# MotionDetectorCamera-Rev4.net
KiCad netlist of a schematic drawn in EAGLE
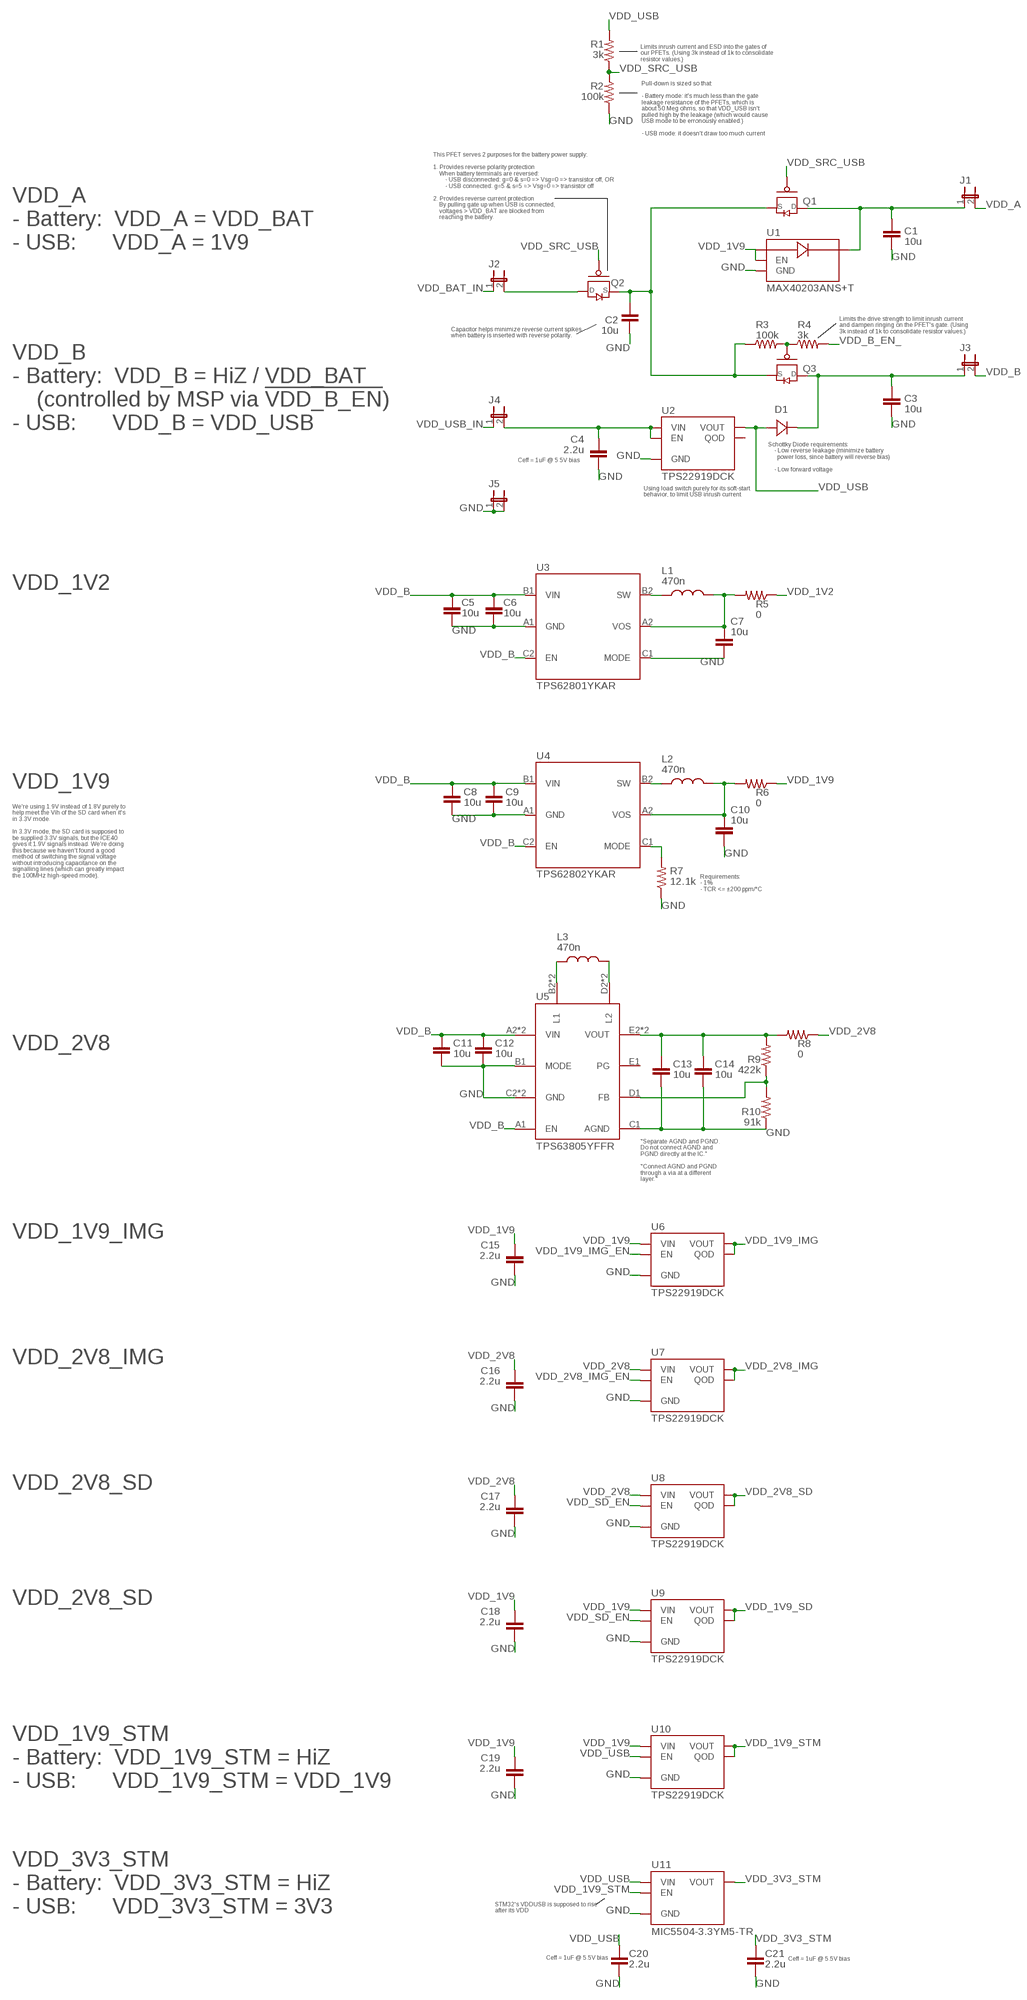
[diagram p0: schematic, sheet 1]
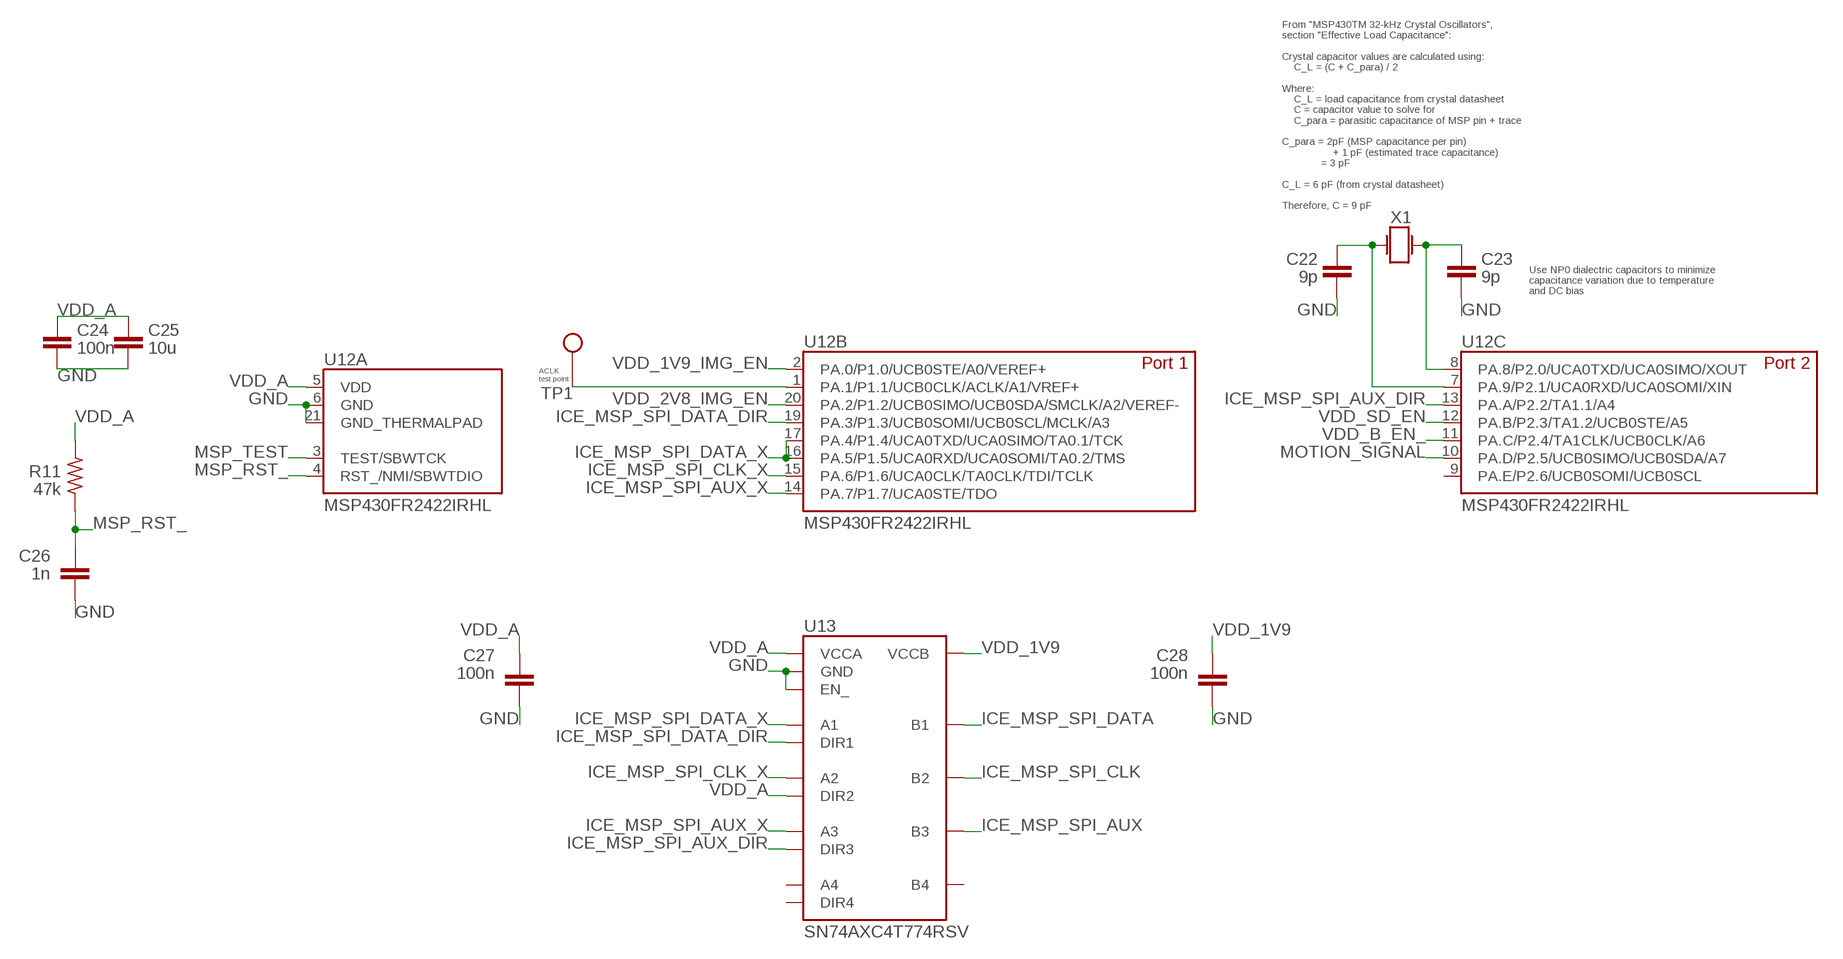
[diagram p1: schematic, sheet 2]
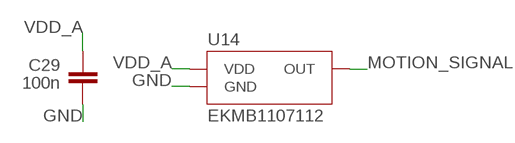
[diagram p2: schematic, sheet 3]
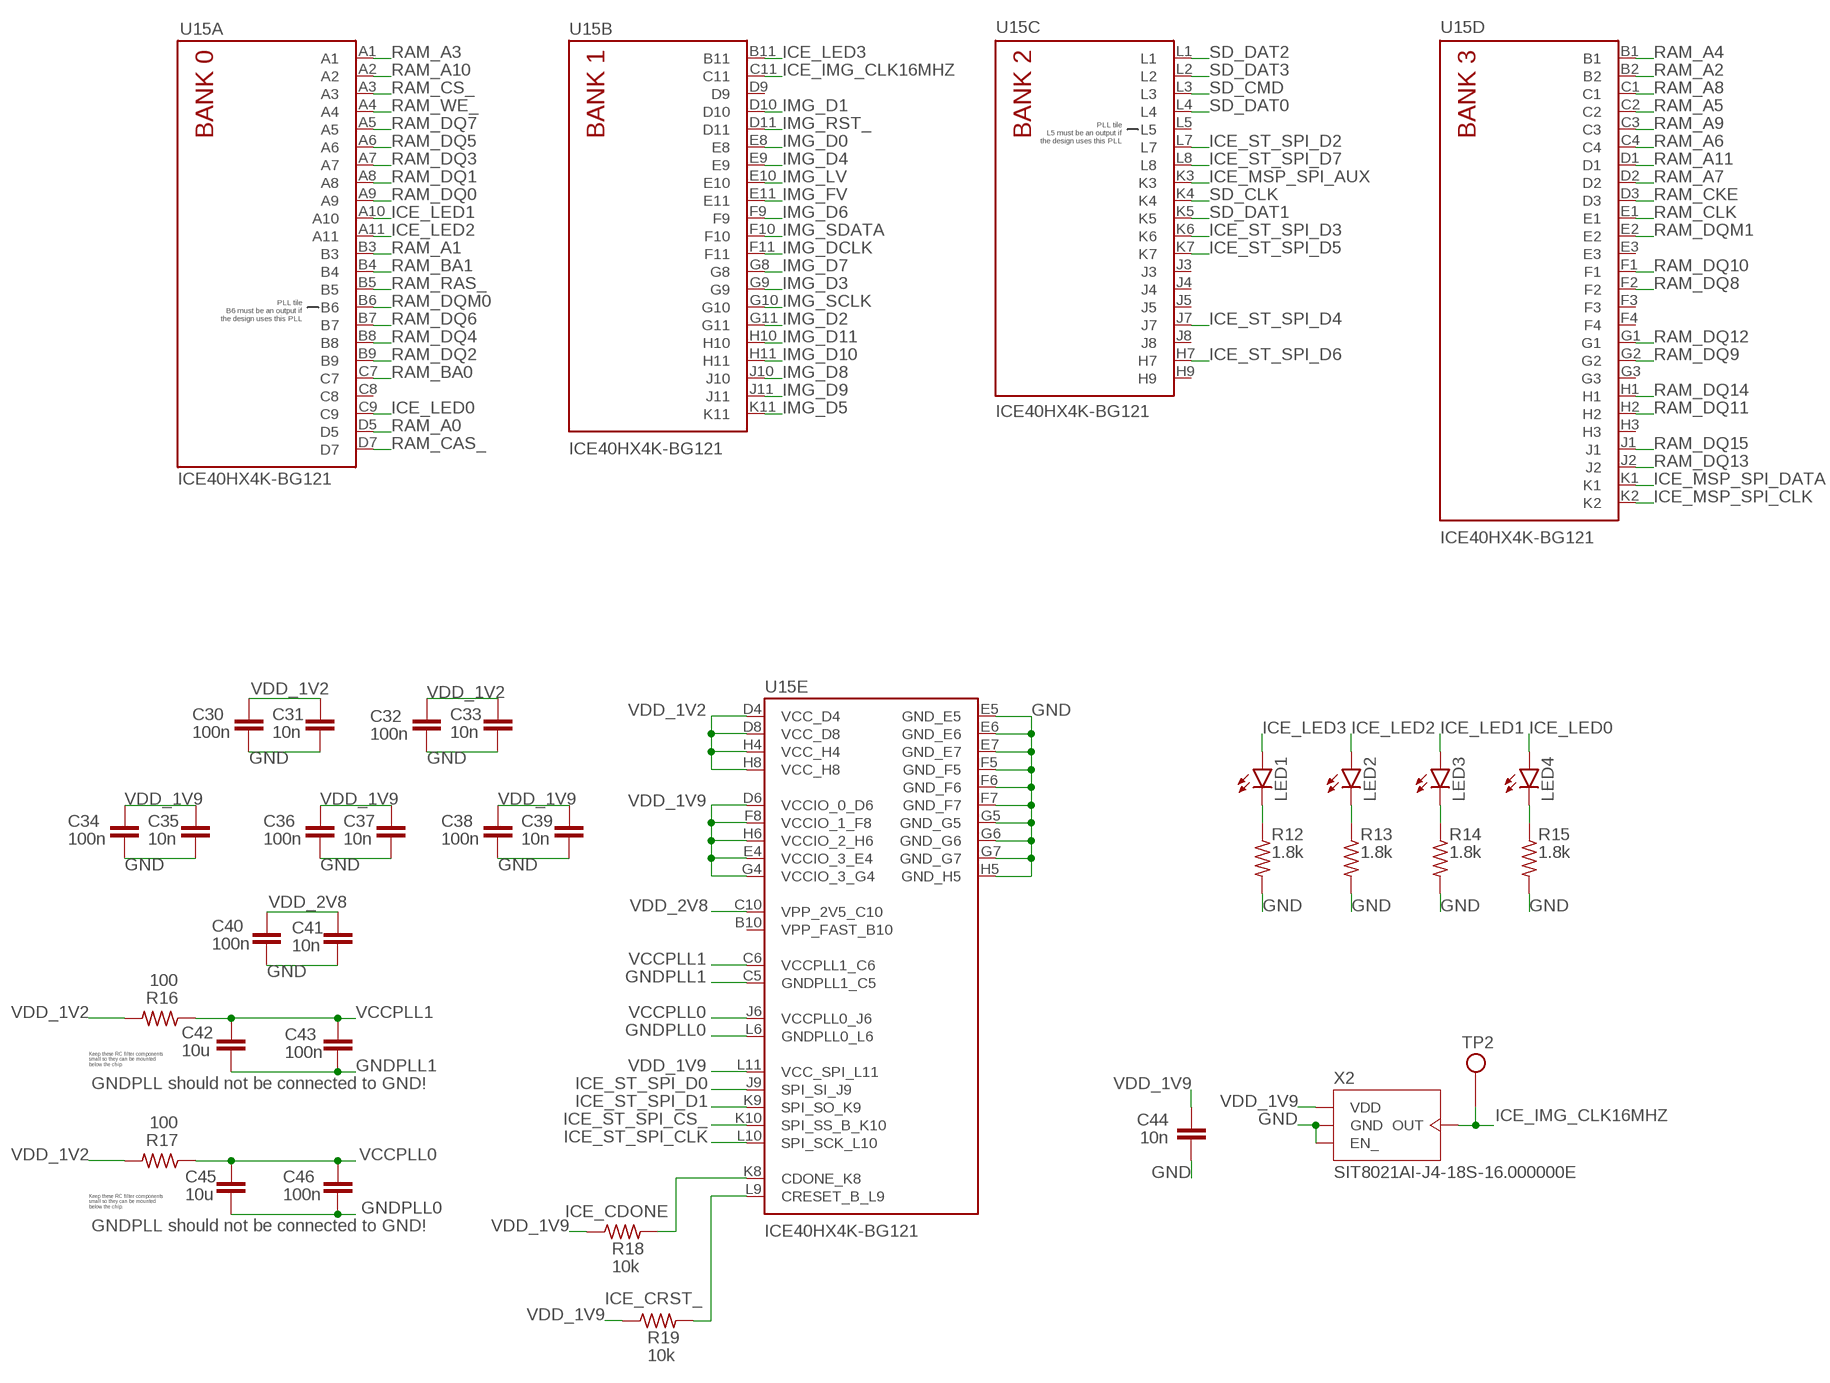
[diagram p3: schematic, sheet 4]
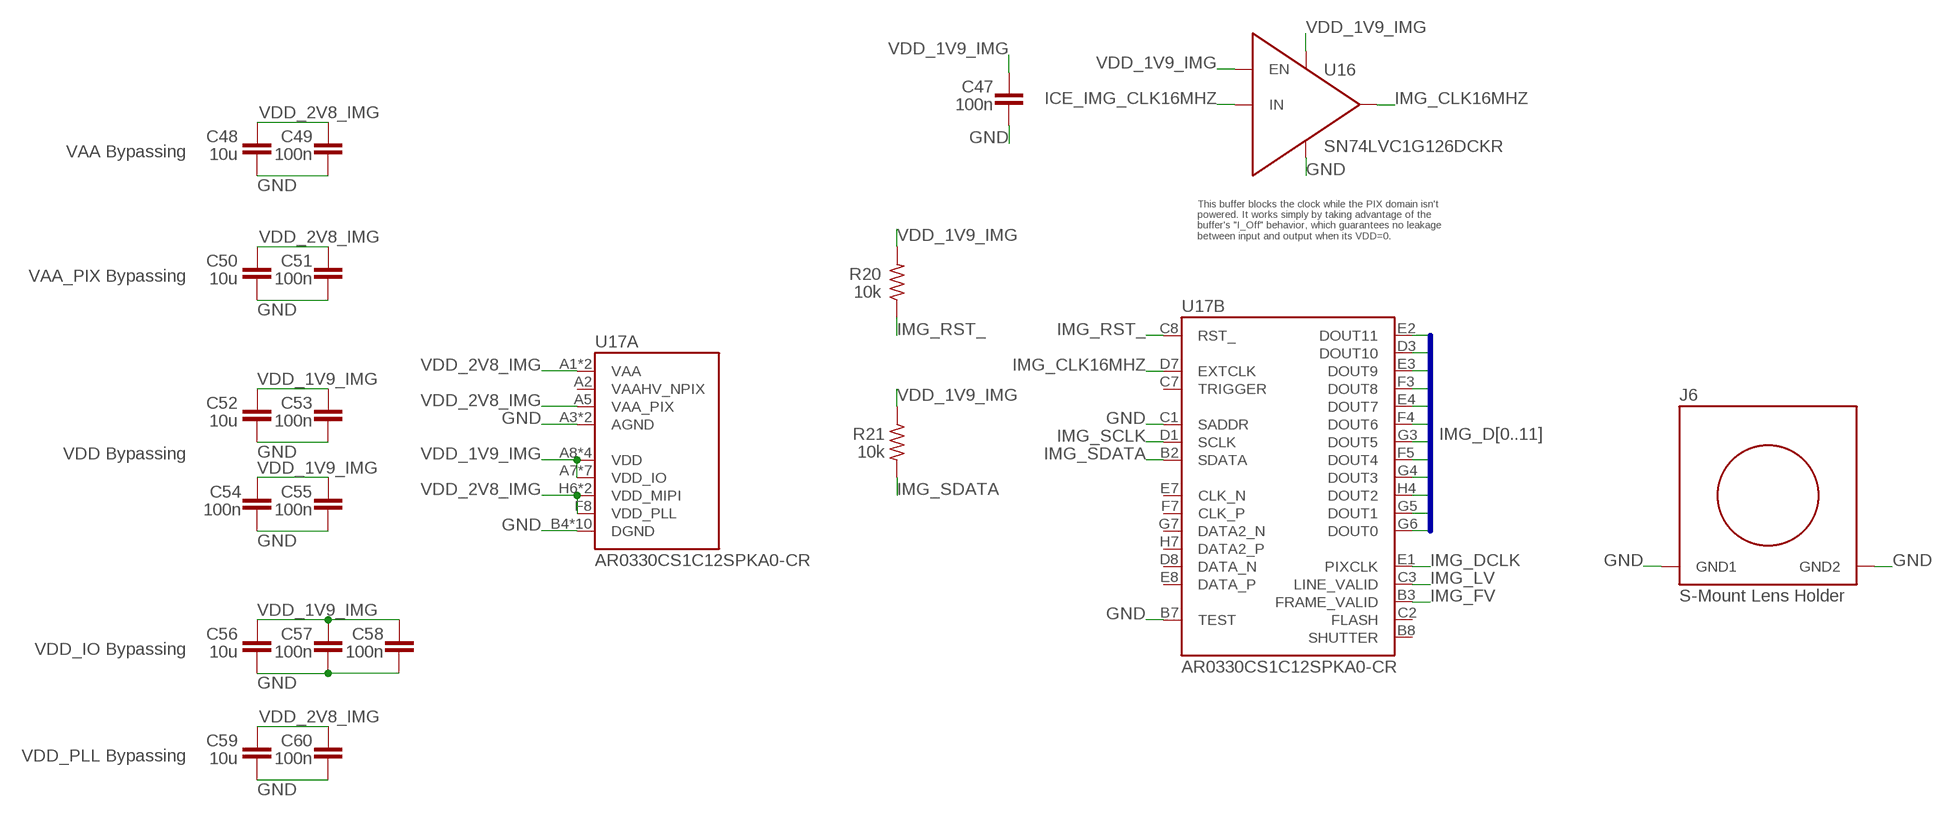
[diagram p4: schematic, sheet 5]
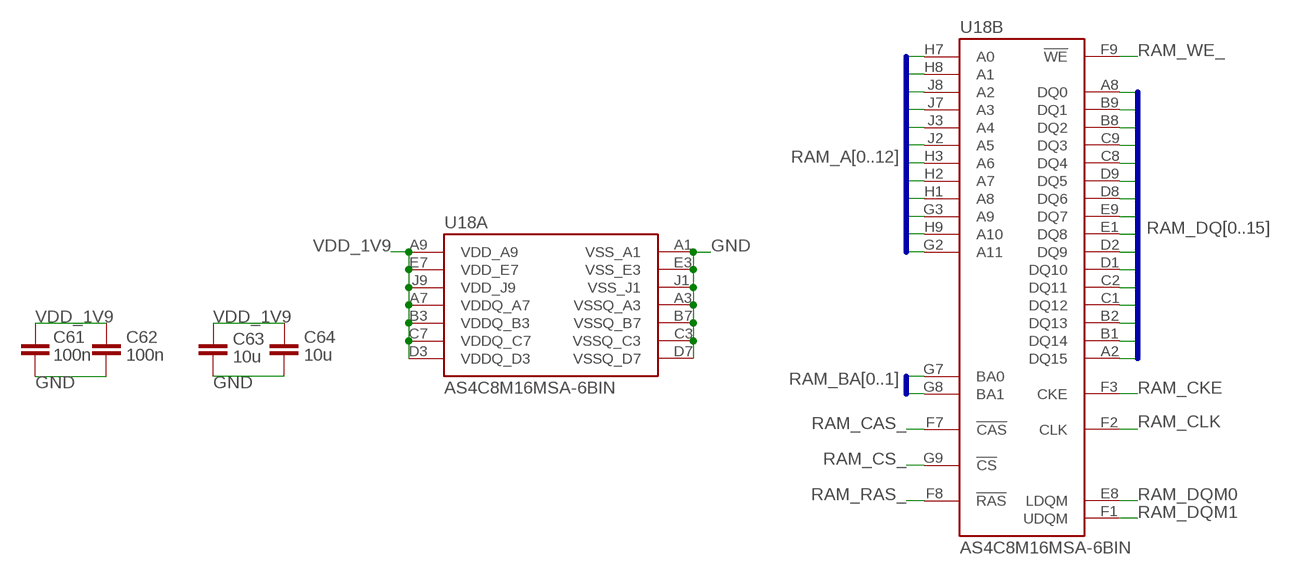
[diagram p5: schematic, sheet 6]
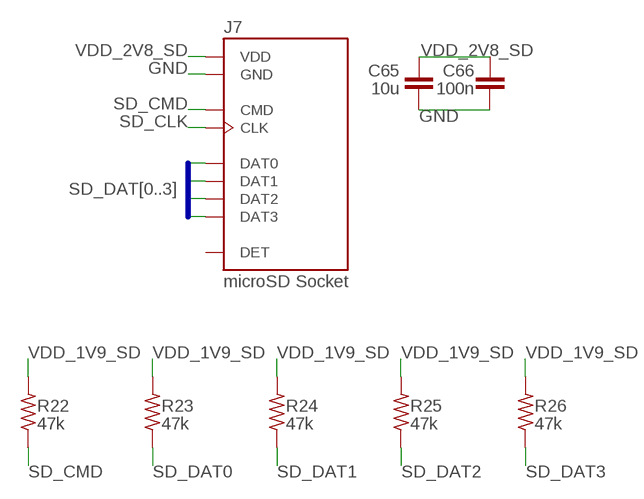
[diagram p6: schematic, sheet 7]
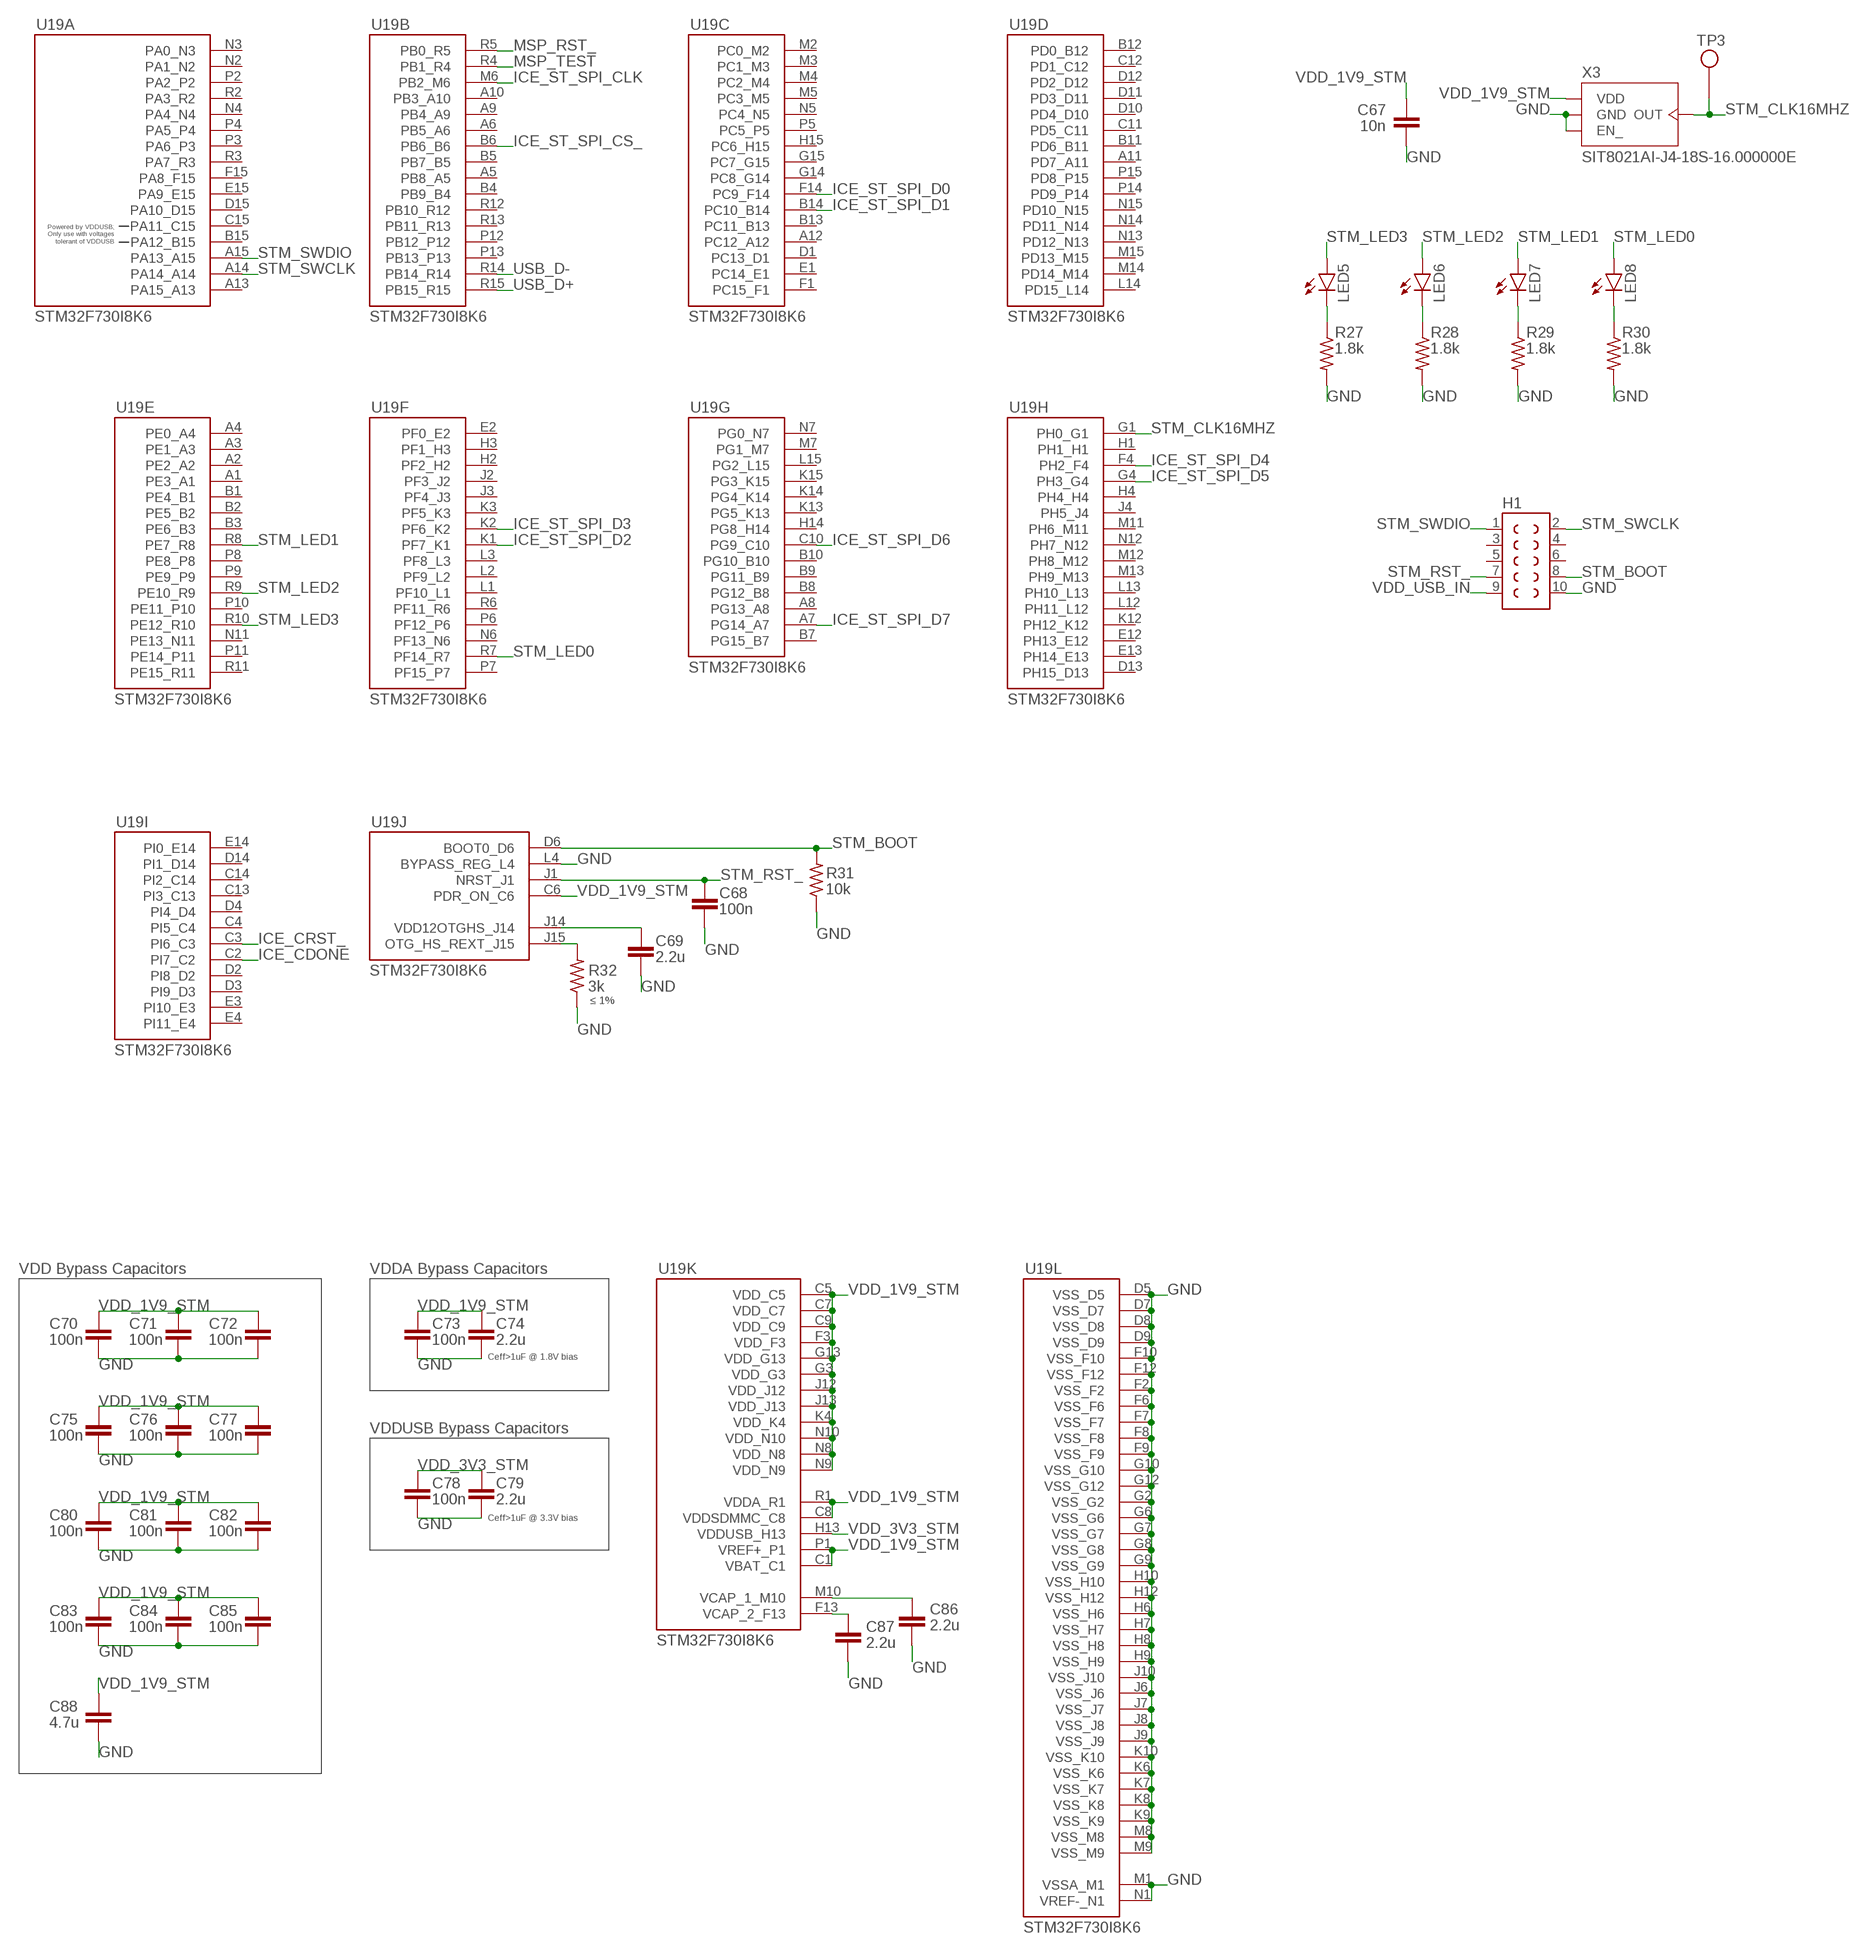
[diagram p7: schematic, sheet 8]
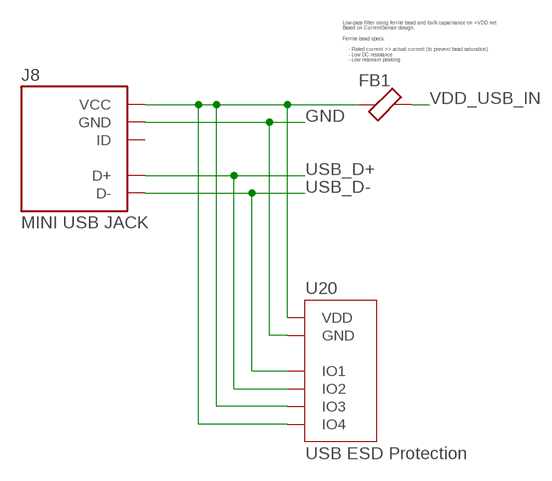
[diagram p8: schematic, sheet 9]

(export (version "E")
  (design (tool "Eeschema 10.0.6"))
  (components
    (comp (ref "C1")
      (value "10u")
      (footprint "eagle-import:0805")
      (fields (field (name "MFG") "Samsung"))
      (libsource (lib "eagle-import") (part "CAPACITOR0805"))
    )
    (comp (ref "C2")
      (value "10u")
      (footprint "eagle-import:0805")
      (fields (field (name "MFG") "Samsung"))
      (libsource (lib "eagle-import") (part "CAPACITOR0805"))
    )
    (comp (ref "C3")
      (value "10u")
      (footprint "eagle-import:0805")
      (fields (field (name "MFG") "Samsung"))
      (libsource (lib "eagle-import") (part "CAPACITOR0805"))
    )
    (comp (ref "C4")
      (value "2.2u")
      (footprint "eagle-import:0402")
      (fields (field (name "MFG") "Taiyo Yuden"))
      (libsource (lib "eagle-import") (part "CAPACITOR0402"))
    )
    (comp (ref "C5")
      (value "10u")
      (footprint "eagle-import:0805")
      (fields (field (name "MFG") "Samsung"))
      (libsource (lib "eagle-import") (part "CAPACITOR0805"))
    )
    (comp (ref "C6")
      (value "10u")
      (footprint "eagle-import:0805")
      (fields (field (name "MFG") "Samsung"))
      (libsource (lib "eagle-import") (part "CAPACITOR0805"))
    )
    (comp (ref "C7")
      (value "10u")
      (footprint "eagle-import:0805")
      (fields (field (name "MFG") "Samsung"))
      (libsource (lib "eagle-import") (part "CAPACITOR0805"))
    )
    (comp (ref "C8")
      (value "10u")
      (footprint "eagle-import:0805")
      (fields (field (name "MFG") "Samsung"))
      (libsource (lib "eagle-import") (part "CAPACITOR0805"))
    )
    (comp (ref "C9")
      (value "10u")
      (footprint "eagle-import:0805")
      (fields (field (name "MFG") "Samsung"))
      (libsource (lib "eagle-import") (part "CAPACITOR0805"))
    )
    (comp (ref "C10")
      (value "10u")
      (footprint "eagle-import:0805")
      (fields (field (name "MFG") "Samsung"))
      (libsource (lib "eagle-import") (part "CAPACITOR0805"))
    )
    (comp (ref "C11")
      (value "10u")
      (footprint "eagle-import:0805")
      (fields (field (name "MFG") "Samsung"))
      (libsource (lib "eagle-import") (part "CAPACITOR0805"))
    )
    (comp (ref "C12")
      (value "10u")
      (footprint "eagle-import:0805")
      (fields (field (name "MFG") "Samsung"))
      (libsource (lib "eagle-import") (part "CAPACITOR0805"))
    )
    (comp (ref "C13")
      (value "10u")
      (footprint "eagle-import:0805")
      (fields (field (name "MFG") "Samsung"))
      (libsource (lib "eagle-import") (part "CAPACITOR0805"))
    )
    (comp (ref "C14")
      (value "10u")
      (footprint "eagle-import:0805")
      (fields (field (name "MFG") "Samsung"))
      (libsource (lib "eagle-import") (part "CAPACITOR0805"))
    )
    (comp (ref "C15")
      (value "2.2u")
      (footprint "eagle-import:0402")
      (fields (field (name "MFG") "Taiyo Yuden"))
      (libsource (lib "eagle-import") (part "CAPACITOR0402"))
    )
    (comp (ref "C16")
      (value "2.2u")
      (footprint "eagle-import:0402")
      (fields (field (name "MFG") "Taiyo Yuden"))
      (libsource (lib "eagle-import") (part "CAPACITOR0402"))
    )
    (comp (ref "C17")
      (value "2.2u")
      (footprint "eagle-import:0402")
      (fields (field (name "MFG") "Taiyo Yuden"))
      (libsource (lib "eagle-import") (part "CAPACITOR0402"))
    )
    (comp (ref "C18")
      (value "2.2u")
      (footprint "eagle-import:0402")
      (fields (field (name "MFG") "Taiyo Yuden"))
      (libsource (lib "eagle-import") (part "CAPACITOR0402"))
    )
    (comp (ref "C19")
      (value "2.2u")
      (footprint "eagle-import:0402")
      (fields (field (name "MFG") "Taiyo Yuden"))
      (libsource (lib "eagle-import") (part "CAPACITOR0402"))
    )
    (comp (ref "C20")
      (value "2.2u")
      (footprint "eagle-import:0402")
      (fields (field (name "MFG") "Taiyo Yuden"))
      (libsource (lib "eagle-import") (part "CAPACITOR0402"))
    )
    (comp (ref "C21")
      (value "2.2u")
      (footprint "eagle-import:0402")
      (fields (field (name "MFG") "Taiyo Yuden"))
      (libsource (lib "eagle-import") (part "CAPACITOR0402"))
    )
    (comp (ref "D1")
      (value "ROHM-RB168MM-40TFTR")
      (footprint "eagle-import:ROHM-RB168MM-40TFTR")
      (fields (field (name "MFG") "ROHM"))
      (libsource (lib "eagle-import") (part "ROHM-RB168MM-40TFTR"))
    )
    (comp (ref "J1")
      (value "JUMPER")
      (footprint "eagle-import:AMPHENOL-10129380-902002ALF")
      (fields (field (name "MFG") "Amphenol"))
      (libsource (lib "eagle-import") (part "JUMPER"))
    )
    (comp (ref "J2")
      (value "JUMPER")
      (footprint "eagle-import:AMPHENOL-10129380-902002ALF")
      (fields (field (name "MFG") "Amphenol"))
      (libsource (lib "eagle-import") (part "JUMPER"))
    )
    (comp (ref "J3")
      (value "JUMPER")
      (footprint "eagle-import:AMPHENOL-10129380-902002ALF")
      (fields (field (name "MFG") "Amphenol"))
      (libsource (lib "eagle-import") (part "JUMPER"))
    )
    (comp (ref "J4")
      (value "JUMPER")
      (footprint "eagle-import:AMPHENOL-10129380-902002ALF")
      (fields (field (name "MFG") "Amphenol"))
      (libsource (lib "eagle-import") (part "JUMPER"))
    )
    (comp (ref "J5")
      (value "JUMPER")
      (footprint "eagle-import:AMPHENOL-10129380-902002ALF")
      (fields (field (name "MFG") "Amphenol"))
      (libsource (lib "eagle-import") (part "JUMPER"))
    )
    (comp (ref "L1")
      (value "470n")
      (footprint "eagle-import:0806")
      (fields (field (name "MFG") "Murata"))
      (libsource (lib "eagle-import") (part "INDUCTOR0806"))
    )
    (comp (ref "L2")
      (value "470n")
      (footprint "eagle-import:0806")
      (fields (field (name "MFG") "Murata"))
      (libsource (lib "eagle-import") (part "INDUCTOR0806"))
    )
    (comp (ref "L3")
      (value "470n")
      (footprint "eagle-import:0806")
      (fields (field (name "MFG") "Murata"))
      (libsource (lib "eagle-import") (part "INDUCTOR0806"))
    )
    (comp (ref "Q1")
      (value "PMOS-NEXPERIA-SOT1220")
      (footprint "eagle-import:NEXPERIA-SOT1220")
      (fields (field (name "MFG") "Nexperia"))
      (libsource (lib "eagle-import") (part "PMOS-NEXPERIA-SOT1220"))
    )
    (comp (ref "Q2")
      (value "PMOS-NEXPERIA-SOT1220")
      (footprint "eagle-import:NEXPERIA-SOT1220")
      (fields (field (name "MFG") "Nexperia"))
      (libsource (lib "eagle-import") (part "PMOS-NEXPERIA-SOT1220"))
    )
    (comp (ref "Q3")
      (value "PMOS-NEXPERIA-SOT1220")
      (footprint "eagle-import:NEXPERIA-SOT1220")
      (fields (field (name "MFG") "Nexperia"))
      (libsource (lib "eagle-import") (part "PMOS-NEXPERIA-SOT1220"))
    )
    (comp (ref "R1")
      (value "3k")
      (footprint "eagle-import:0402")
      (fields (field (name "MFG") "Yageo"))
      (libsource (lib "eagle-import") (part "RESISTOR0402"))
    )
    (comp (ref "R2")
      (value "100k")
      (footprint "eagle-import:0402")
      (fields (field (name "MFG") "Yageo"))
      (libsource (lib "eagle-import") (part "RESISTOR0402"))
    )
    (comp (ref "R3")
      (value "100k")
      (footprint "eagle-import:0402")
      (fields (field (name "MFG") "Yageo"))
      (libsource (lib "eagle-import") (part "RESISTOR0402"))
    )
    (comp (ref "R4")
      (value "3k")
      (footprint "eagle-import:0402")
      (fields (field (name "MFG") "Yageo"))
      (libsource (lib "eagle-import") (part "RESISTOR0402"))
    )
    (comp (ref "R5")
      (value "0")
      (footprint "eagle-import:0805")
      (fields (field (name "MFG") "Yageo"))
      (libsource (lib "eagle-import") (part "RESISTOR0805"))
    )
    (comp (ref "R6")
      (value "0")
      (footprint "eagle-import:0805")
      (fields (field (name "MFG") "Yageo"))
      (libsource (lib "eagle-import") (part "RESISTOR0805"))
    )
    (comp (ref "R7")
      (value "12.1k")
      (footprint "eagle-import:0402")
      (fields (field (name "MFG") "Walsin"))
      (libsource (lib "eagle-import") (part "RESISTOR0402"))
    )
    (comp (ref "R8")
      (value "0")
      (footprint "eagle-import:0805")
      (fields (field (name "MFG") "Yageo"))
      (libsource (lib "eagle-import") (part "RESISTOR0805"))
    )
    (comp (ref "R9")
      (value "422k")
      (footprint "eagle-import:0402")
      (fields (field (name "MFG") "Bourns"))
      (libsource (lib "eagle-import") (part "RESISTOR0402"))
    )
    (comp (ref "R10")
      (value "91k")
      (footprint "eagle-import:0402")
      (fields (field (name "MFG") "Bourns"))
      (libsource (lib "eagle-import") (part "RESISTOR0402"))
    )
    (comp (ref "U1")
      (value "MAXIM-MAX40203ANS+T")
      (footprint "eagle-import:MAXIM-MAX40203ANS+T")
      (fields (field (name "PN") "MAX40203ANS+T") (field (name "MFG") "Maxim Integrated"))
      (libsource (lib "eagle-import") (part "MAXIM-MAX40203ANS+T"))
    )
    (comp (ref "U2")
      (value "TI-TPS22919DCK")
      (footprint "eagle-import:TI-TPS22919DCK")
      (fields (field (name "PN") "TPS22919DCK") (field (name "MFG") "Texas Instruments"))
      (libsource (lib "eagle-import") (part "TI-TPS22919DCK"))
    )
    (comp (ref "U3")
      (value "TI-TPS6280XYKAR")
      (footprint "eagle-import:TI-TPS6280XYKAR")
      (fields (field (name "MFG") "Texas Instruments") (field (name "PN") "TPS62801YKAR"))
      (libsource (lib "eagle-import") (part "TI-TPS6280XYKAR"))
    )
    (comp (ref "U4")
      (value "TI-TPS6280XYKAR")
      (footprint "eagle-import:TI-TPS6280XYKAR")
      (fields (field (name "MFG") "Texas Instruments") (field (name "PN") "TPS62802YKAR"))
      (libsource (lib "eagle-import") (part "TI-TPS6280XYKAR"))
    )
    (comp (ref "U5")
      (value "TI-TPS63805YFFR")
      (footprint "eagle-import:TI-TPS63805YFFR")
      (fields (field (name "PN") "TPS63805YFFR") (field (name "MFG") "Texas Instruments"))
      (libsource (lib "eagle-import") (part "TI-TPS63805YFFR"))
    )
    (comp (ref "U6")
      (value "TI-TPS22919DCK")
      (footprint "eagle-import:TI-TPS22919DCK")
      (fields (field (name "PN") "TPS22919DCK") (field (name "MFG") "Texas Instruments"))
      (libsource (lib "eagle-import") (part "TI-TPS22919DCK"))
    )
    (comp (ref "U7")
      (value "TI-TPS22919DCK")
      (footprint "eagle-import:TI-TPS22919DCK")
      (fields (field (name "PN") "TPS22919DCK") (field (name "MFG") "Texas Instruments"))
      (libsource (lib "eagle-import") (part "TI-TPS22919DCK"))
    )
    (comp (ref "U8")
      (value "TI-TPS22919DCK")
      (footprint "eagle-import:TI-TPS22919DCK")
      (fields (field (name "PN") "TPS22919DCK") (field (name "MFG") "Texas Instruments"))
      (libsource (lib "eagle-import") (part "TI-TPS22919DCK"))
    )
    (comp (ref "U9")
      (value "TI-TPS22919DCK")
      (footprint "eagle-import:TI-TPS22919DCK")
      (fields (field (name "PN") "TPS22919DCK") (field (name "MFG") "Texas Instruments"))
      (libsource (lib "eagle-import") (part "TI-TPS22919DCK"))
    )
    (comp (ref "U10")
      (value "TI-TPS22919DCK")
      (footprint "eagle-import:TI-TPS22919DCK")
      (fields (field (name "PN") "TPS22919DCK") (field (name "MFG") "Texas Instruments"))
      (libsource (lib "eagle-import") (part "TI-TPS22919DCK"))
    )
    (comp (ref "U11")
      (value "MICROCHIP-MIC550X")
      (footprint "eagle-import:MICROCHIP-MIC550X-SOT23-5")
      (fields (field (name "MFG") "Microchip") (field (name "PN") "MIC5504-3.3YM5-TR"))
      (libsource (lib "eagle-import") (part "MICROCHIP-MIC550X"))
    )
    (comp (ref "C29")
      (value "100n")
      (footprint "eagle-import:0402")
      (fields (field (name "MFG") "Murata"))
      (libsource (lib "eagle-import") (part "CAPACITOR0402"))
    )
    (comp (ref "U14")
      (value "PANASONIC-EKMB110711X")
      (footprint "eagle-import:PANASONIC-EKMB110711X")
      (fields (field (name "MFG") "Panasonic") (field (name "PN") "EKMB1107112"))
      (libsource (lib "eagle-import") (part "PANASONIC-EKMB110711X"))
    )
    (comp (ref "C22")
      (value "9p")
      (footprint "eagle-import:0402")
      (fields (field (name "MFG") "Yageo"))
      (libsource (lib "eagle-import") (part "CAPACITOR0402"))
    )
    (comp (ref "C23")
      (value "9p")
      (footprint "eagle-import:0402")
      (fields (field (name "MFG") "Yageo"))
      (libsource (lib "eagle-import") (part "CAPACITOR0402"))
    )
    (comp (ref "C24")
      (value "100n")
      (footprint "eagle-import:0402")
      (fields (field (name "MFG") "Murata"))
      (libsource (lib "eagle-import") (part "CAPACITOR0402"))
    )
    (comp (ref "C25")
      (value "10u")
      (footprint "eagle-import:0805")
      (fields (field (name "MFG") "Samsung"))
      (libsource (lib "eagle-import") (part "CAPACITOR0805"))
    )
    (comp (ref "C26")
      (value "1n")
      (footprint "eagle-import:0402")
      (fields (field (name "MFG") "Yageo"))
      (libsource (lib "eagle-import") (part "CAPACITOR0402"))
    )
    (comp (ref "C27")
      (value "100n")
      (footprint "eagle-import:0402")
      (fields (field (name "MFG") "Murata"))
      (libsource (lib "eagle-import") (part "CAPACITOR0402"))
    )
    (comp (ref "C28")
      (value "100n")
      (footprint "eagle-import:0402")
      (fields (field (name "MFG") "Murata"))
      (libsource (lib "eagle-import") (part "CAPACITOR0402"))
    )
    (comp (ref "R11")
      (value "47k")
      (footprint "eagle-import:0402")
      (fields (field (name "MFG") "Walsin"))
      (libsource (lib "eagle-import") (part "RESISTOR0402"))
    )
    (comp (ref "TP1")
      (value "TEST-POINT")
      (footprint "eagle-import:TEST-POINT")
      (libsource (lib "eagle-import") (part "TEST-POINT"))
    )
    (comp (ref "U12")
      (value "TI-MSP430FR2422IRHL")
      (footprint "eagle-import:TI-MSP430FR2422IRHL")
      (fields (field (name "PN") "MSP430FR2422IRHL") (field (name "MFG") "Texas Instruments"))
      (libsource (lib "eagle-import") (part "TI-MSP430FR2422IRHL"))
    )
    (comp (ref "U13")
      (value "TI-SN74AXC4T774RSV")
      (footprint "eagle-import:TI-SN74AXC4T774RSV")
      (fields (field (name "PN") "SN74AXC4T774RSV") (field (name "MFG") "Texas Instruments"))
      (libsource (lib "eagle-import") (part "TI-SN74AXC4T774RSV"))
    )
    (comp (ref "X1")
      (value "EPSON-MC-306")
      (footprint "eagle-import:EPSON-MC-306")
      (fields (field (name "MFG") "Epson") (field (name "PN") "MC-306 32.7680K-E3:ROHS"))
      (libsource (lib "eagle-import") (part "EPSON-MC-306"))
    )
    (comp (ref "C47")
      (value "100n")
      (footprint "eagle-import:0402")
      (fields (field (name "MFG") "Murata"))
      (libsource (lib "eagle-import") (part "CAPACITOR0402"))
    )
    (comp (ref "C48")
      (value "10u")
      (footprint "eagle-import:0805")
      (fields (field (name "MFG") "Samsung"))
      (libsource (lib "eagle-import") (part "CAPACITOR0805"))
    )
    (comp (ref "C49")
      (value "100n")
      (footprint "eagle-import:0402")
      (fields (field (name "MFG") "Murata"))
      (libsource (lib "eagle-import") (part "CAPACITOR0402"))
    )
    (comp (ref "C50")
      (value "10u")
      (footprint "eagle-import:0805")
      (fields (field (name "MFG") "Samsung"))
      (libsource (lib "eagle-import") (part "CAPACITOR0805"))
    )
    (comp (ref "C51")
      (value "100n")
      (footprint "eagle-import:0402")
      (fields (field (name "MFG") "Murata"))
      (libsource (lib "eagle-import") (part "CAPACITOR0402"))
    )
    (comp (ref "C52")
      (value "10u")
      (footprint "eagle-import:0805")
      (fields (field (name "MFG") "Samsung"))
      (libsource (lib "eagle-import") (part "CAPACITOR0805"))
    )
    (comp (ref "C53")
      (value "100n")
      (footprint "eagle-import:0402")
      (fields (field (name "MFG") "Murata"))
      (libsource (lib "eagle-import") (part "CAPACITOR0402"))
    )
    (comp (ref "C54")
      (value "100n")
      (footprint "eagle-import:0402")
      (fields (field (name "MFG") "Murata"))
      (libsource (lib "eagle-import") (part "CAPACITOR0402"))
    )
    (comp (ref "C55")
      (value "100n")
      (footprint "eagle-import:0402")
      (fields (field (name "MFG") "Murata"))
      (libsource (lib "eagle-import") (part "CAPACITOR0402"))
    )
    (comp (ref "C56")
      (value "10u")
      (footprint "eagle-import:0805")
      (fields (field (name "MFG") "Samsung"))
      (libsource (lib "eagle-import") (part "CAPACITOR0805"))
    )
    (comp (ref "C57")
      (value "100n")
      (footprint "eagle-import:0402")
      (fields (field (name "MFG") "Murata"))
      (libsource (lib "eagle-import") (part "CAPACITOR0402"))
    )
    (comp (ref "C58")
      (value "100n")
      (footprint "eagle-import:0402")
      (fields (field (name "MFG") "Murata"))
      (libsource (lib "eagle-import") (part "CAPACITOR0402"))
    )
    (comp (ref "C59")
      (value "10u")
      (footprint "eagle-import:0805")
      (fields (field (name "MFG") "Samsung"))
      (libsource (lib "eagle-import") (part "CAPACITOR0805"))
    )
    (comp (ref "C60")
      (value "100n")
      (footprint "eagle-import:0402")
      (fields (field (name "MFG") "Murata"))
      (libsource (lib "eagle-import") (part "CAPACITOR0402"))
    )
    (comp (ref "J6")
      (value "S-MOUNT-LENS-HOLDER")
      (footprint "eagle-import:S-MOUNT-LENS-HOLDER")
      (fields (field (name "MFG") "Marshall Electronics"))
      (libsource (lib "eagle-import") (part "S-MOUNT-LENS-HOLDER"))
    )
    (comp (ref "R20")
      (value "10k")
      (footprint "eagle-import:0402")
      (fields (field (name "MFG") "Yageo"))
      (libsource (lib "eagle-import") (part "RESISTOR0402"))
    )
    (comp (ref "R21")
      (value "10k")
      (footprint "eagle-import:0402")
      (fields (field (name "MFG") "Yageo"))
      (libsource (lib "eagle-import") (part "RESISTOR0402"))
    )
    (comp (ref "U16")
      (value "TI-SN74LVC1G126")
      (footprint "eagle-import:TI-SN74LVC1G126DCK")
      (fields (field (name "MFG") "Texas Instruments") (field (name "PN") "SN74LVC1G126DCKR"))
      (libsource (lib "eagle-import") (part "TI-SN74LVC1G126"))
    )
    (comp (ref "U17")
      (value "ON-AR0330CS1C12SPKA0")
      (footprint "eagle-import:ON-AR0330CS1C12SPKA0")
      (fields (field (name "MFG") "ON Semiconductor") (field (name "PN") "AR0330CS1C12SPKA0-CR"))
      (libsource (lib "eagle-import") (part "ON-AR0330CS1C12SPKA0"))
    )
    (comp (ref "FB1")
      (value "FERRITE-BEAD0402")
      (footprint "eagle-import:0402")
      (fields (field (name "MFG") "Taiyo Yuden"))
      (libsource (lib "eagle-import") (part "FERRITE-BEAD0402"))
    )
    (comp (ref "J8")
      (value "MINI-USB-JACK")
      (footprint "eagle-import:AMPHENOL-10033526-N3222MLF")
      (fields (field (name "MFG") "Amphenol FCI"))
      (libsource (lib "eagle-import") (part "MINI-USB-JACK"))
    )
    (comp (ref "U20")
      (value "DIODESINC-DT1446-04V-7")
      (footprint "eagle-import:DIODESINC-DT1446-04V-7")
      (fields (field (name "MFG") "Diodes Incorporated"))
      (libsource (lib "eagle-import") (part "DIODESINC-DT1446-04V-7"))
    )
    (comp (ref "C61")
      (value "100n")
      (footprint "eagle-import:0402")
      (fields (field (name "MFG") "Murata"))
      (libsource (lib "eagle-import") (part "CAPACITOR0402"))
    )
    (comp (ref "C62")
      (value "100n")
      (footprint "eagle-import:0402")
      (fields (field (name "MFG") "Murata"))
      (libsource (lib "eagle-import") (part "CAPACITOR0402"))
    )
    (comp (ref "C63")
      (value "10u")
      (footprint "eagle-import:0805")
      (fields (field (name "MFG") "Samsung"))
      (libsource (lib "eagle-import") (part "CAPACITOR0805"))
    )
    (comp (ref "C64")
      (value "10u")
      (footprint "eagle-import:0805")
      (fields (field (name "MFG") "Samsung"))
      (libsource (lib "eagle-import") (part "CAPACITOR0805"))
    )
    (comp (ref "U18")
      (value "ALLIANCE-AS4C8M16MSA-6BIN")
      (footprint "eagle-import:ALLIANCE-AS4C8M16MSA-6BIN")
      (fields (field (name "PN") "AS4C8M16MSA-6BIN") (field (name "MFG") "Alliance Memory"))
      (libsource (lib "eagle-import") (part "ALLIANCE-AS4C8M16MSA-6BIN"))
    )
    (comp (ref "C67")
      (value "10n")
      (footprint "eagle-import:0402")
      (fields (field (name "MFG") "Samsung"))
      (libsource (lib "eagle-import") (part "CAPACITOR0402"))
    )
    (comp (ref "C68")
      (value "100n")
      (footprint "eagle-import:0402")
      (fields (field (name "MFG") "Murata"))
      (libsource (lib "eagle-import") (part "CAPACITOR0402"))
    )
    (comp (ref "C69")
      (value "2.2u")
      (footprint "eagle-import:0402")
      (fields (field (name "MFG") "Taiyo Yuden"))
      (libsource (lib "eagle-import") (part "CAPACITOR0402"))
    )
    (comp (ref "C70")
      (value "100n")
      (footprint "eagle-import:0402")
      (fields (field (name "MFG") "Murata"))
      (libsource (lib "eagle-import") (part "CAPACITOR0402"))
    )
    (comp (ref "C71")
      (value "100n")
      (footprint "eagle-import:0402")
      (fields (field (name "MFG") "Murata"))
      (libsource (lib "eagle-import") (part "CAPACITOR0402"))
    )
    (comp (ref "C72")
      (value "100n")
      (footprint "eagle-import:0402")
      (fields (field (name "MFG") "Murata"))
      (libsource (lib "eagle-import") (part "CAPACITOR0402"))
    )
    (comp (ref "C73")
      (value "100n")
      (footprint "eagle-import:0402")
      (fields (field (name "MFG") "Murata"))
      (libsource (lib "eagle-import") (part "CAPACITOR0402"))
    )
    (comp (ref "C74")
      (value "2.2u")
      (footprint "eagle-import:0402")
      (fields (field (name "MFG") "Taiyo Yuden"))
      (libsource (lib "eagle-import") (part "CAPACITOR0402"))
    )
    (comp (ref "C75")
      (value "100n")
      (footprint "eagle-import:0402")
      (fields (field (name "MFG") "Murata"))
      (libsource (lib "eagle-import") (part "CAPACITOR0402"))
    )
    (comp (ref "C76")
      (value "100n")
      (footprint "eagle-import:0402")
      (fields (field (name "MFG") "Murata"))
      (libsource (lib "eagle-import") (part "CAPACITOR0402"))
    )
    (comp (ref "C77")
      (value "100n")
      (footprint "eagle-import:0402")
      (fields (field (name "MFG") "Murata"))
      (libsource (lib "eagle-import") (part "CAPACITOR0402"))
    )
    (comp (ref "C78")
      (value "100n")
      (footprint "eagle-import:0402")
      (fields (field (name "MFG") "Murata"))
      (libsource (lib "eagle-import") (part "CAPACITOR0402"))
    )
    (comp (ref "C79")
      (value "2.2u")
      (footprint "eagle-import:0402")
      (fields (field (name "MFG") "Taiyo Yuden"))
      (libsource (lib "eagle-import") (part "CAPACITOR0402"))
    )
    (comp (ref "C80")
      (value "100n")
      (footprint "eagle-import:0402")
      (fields (field (name "MFG") "Murata"))
      (libsource (lib "eagle-import") (part "CAPACITOR0402"))
    )
    (comp (ref "C81")
      (value "100n")
      (footprint "eagle-import:0402")
      (fields (field (name "MFG") "Murata"))
      (libsource (lib "eagle-import") (part "CAPACITOR0402"))
    )
    (comp (ref "C82")
      (value "100n")
      (footprint "eagle-import:0402")
      (fields (field (name "MFG") "Murata"))
      (libsource (lib "eagle-import") (part "CAPACITOR0402"))
    )
    (comp (ref "C83")
      (value "100n")
      (footprint "eagle-import:0402")
      (fields (field (name "MFG") "Murata"))
      (libsource (lib "eagle-import") (part "CAPACITOR0402"))
    )
    (comp (ref "C84")
      (value "100n")
      (footprint "eagle-import:0402")
      (fields (field (name "MFG") "Murata"))
      (libsource (lib "eagle-import") (part "CAPACITOR0402"))
    )
    (comp (ref "C85")
      (value "100n")
      (footprint "eagle-import:0402")
      (fields (field (name "MFG") "Murata"))
      (libsource (lib "eagle-import") (part "CAPACITOR0402"))
    )
    (comp (ref "C86")
      (value "2.2u")
      (footprint "eagle-import:0402")
      (fields (field (name "MFG") "Taiyo Yuden"))
      (libsource (lib "eagle-import") (part "CAPACITOR0402"))
    )
    (comp (ref "C87")
      (value "2.2u")
      (footprint "eagle-import:0402")
      (fields (field (name "MFG") "Taiyo Yuden"))
      (libsource (lib "eagle-import") (part "CAPACITOR0402"))
    )
    (comp (ref "C88")
      (value "4.7u")
      (footprint "eagle-import:0603")
      (fields (field (name "MFG") "Taiyo Yuden"))
      (libsource (lib "eagle-import") (part "CAPACITOR0603"))
    )
    (comp (ref "H1")
      (value "HEADER-2X5")
      (footprint "eagle-import:TEC-1-2314844-0")
      (fields (field (name "MFG") "TE Connectivity"))
      (libsource (lib "eagle-import") (part "HEADER-2X5"))
    )
    (comp (ref "LED5")
      (value "LED")
      (footprint "eagle-import:LED-0603")
      (fields (field (name "MFG") "OSRAM"))
      (libsource (lib "eagle-import") (part "LED"))
    )
    (comp (ref "LED6")
      (value "LED")
      (footprint "eagle-import:LED-0603")
      (fields (field (name "MFG") "OSRAM"))
      (libsource (lib "eagle-import") (part "LED"))
    )
    (comp (ref "LED7")
      (value "LED")
      (footprint "eagle-import:LED-0603")
      (fields (field (name "MFG") "OSRAM"))
      (libsource (lib "eagle-import") (part "LED"))
    )
    (comp (ref "LED8")
      (value "LED")
      (footprint "eagle-import:LED-0603")
      (fields (field (name "MFG") "OSRAM"))
      (libsource (lib "eagle-import") (part "LED"))
    )
    (comp (ref "R27")
      (value "1.8k")
      (footprint "eagle-import:0402")
      (fields (field (name "MFG") "TE Connectivity"))
      (libsource (lib "eagle-import") (part "RESISTOR0402"))
    )
    (comp (ref "R28")
      (value "1.8k")
      (footprint "eagle-import:0402")
      (fields (field (name "MFG") "TE Connectivity"))
      (libsource (lib "eagle-import") (part "RESISTOR0402"))
    )
    (comp (ref "R29")
      (value "1.8k")
      (footprint "eagle-import:0402")
      (fields (field (name "MFG") "TE Connectivity"))
      (libsource (lib "eagle-import") (part "RESISTOR0402"))
    )
    (comp (ref "R30")
      (value "1.8k")
      (footprint "eagle-import:0402")
      (fields (field (name "MFG") "TE Connectivity"))
      (libsource (lib "eagle-import") (part "RESISTOR0402"))
    )
    (comp (ref "R31")
      (value "10k")
      (footprint "eagle-import:0402")
      (fields (field (name "MFG") "Yageo"))
      (libsource (lib "eagle-import") (part "RESISTOR0402"))
    )
    (comp (ref "R32")
      (value "3k")
      (footprint "eagle-import:0402")
      (fields (field (name "MFG") "Yageo"))
      (libsource (lib "eagle-import") (part "RESISTOR0402"))
    )
    (comp (ref "TP3")
      (value "TEST-POINT")
      (footprint "eagle-import:TEST-POINT")
      (libsource (lib "eagle-import") (part "TEST-POINT"))
    )
    (comp (ref "U19")
      (value "STM-STM32F730")
      (footprint "eagle-import:STM-STM32F730I8")
      (fields (field (name "MFG") "STMicroelectronics") (field (name "PN") "STM32F730I8K6"))
      (libsource (lib "eagle-import") (part "STM-STM32F730"))
    )
    (comp (ref "X3")
      (value "SITIME-SIT8021")
      (footprint "eagle-import:SITIME-SIT8021")
      (fields (field (name "MFG") "SiTime") (field (name "PN") "SIT8021AI-J4-18S-16.000000E"))
      (libsource (lib "eagle-import") (part "SITIME-SIT8021"))
    )
    (comp (ref "C30")
      (value "100n")
      (footprint "eagle-import:0402")
      (fields (field (name "MFG") "Murata"))
      (libsource (lib "eagle-import") (part "CAPACITOR0402"))
    )
    (comp (ref "C31")
      (value "10n")
      (footprint "eagle-import:0402")
      (fields (field (name "MFG") "Samsung"))
      (libsource (lib "eagle-import") (part "CAPACITOR0402"))
    )
    (comp (ref "C32")
      (value "100n")
      (footprint "eagle-import:0402")
      (fields (field (name "MFG") "Murata"))
      (libsource (lib "eagle-import") (part "CAPACITOR0402"))
    )
    (comp (ref "C33")
      (value "10n")
      (footprint "eagle-import:0402")
      (fields (field (name "MFG") "Samsung"))
      (libsource (lib "eagle-import") (part "CAPACITOR0402"))
    )
    (comp (ref "C34")
      (value "100n")
      (footprint "eagle-import:0402")
      (fields (field (name "MFG") "Murata"))
      (libsource (lib "eagle-import") (part "CAPACITOR0402"))
    )
    (comp (ref "C35")
      (value "10n")
      (footprint "eagle-import:0402")
      (fields (field (name "MFG") "Samsung"))
      (libsource (lib "eagle-import") (part "CAPACITOR0402"))
    )
    (comp (ref "C36")
      (value "100n")
      (footprint "eagle-import:0402")
      (fields (field (name "MFG") "Murata"))
      (libsource (lib "eagle-import") (part "CAPACITOR0402"))
    )
    (comp (ref "C37")
      (value "10n")
      (footprint "eagle-import:0402")
      (fields (field (name "MFG") "Samsung"))
      (libsource (lib "eagle-import") (part "CAPACITOR0402"))
    )
    (comp (ref "C38")
      (value "100n")
      (footprint "eagle-import:0402")
      (fields (field (name "MFG") "Murata"))
      (libsource (lib "eagle-import") (part "CAPACITOR0402"))
    )
    (comp (ref "C39")
      (value "10n")
      (footprint "eagle-import:0402")
      (fields (field (name "MFG") "Samsung"))
      (libsource (lib "eagle-import") (part "CAPACITOR0402"))
    )
    (comp (ref "C40")
      (value "100n")
      (footprint "eagle-import:0402")
      (fields (field (name "MFG") "Murata"))
      (libsource (lib "eagle-import") (part "CAPACITOR0402"))
    )
    (comp (ref "C41")
      (value "10n")
      (footprint "eagle-import:0402")
      (fields (field (name "MFG") "Samsung"))
      (libsource (lib "eagle-import") (part "CAPACITOR0402"))
    )
    (comp (ref "C42")
      (value "10u")
      (footprint "eagle-import:0805")
      (fields (field (name "MFG") "Samsung"))
      (libsource (lib "eagle-import") (part "CAPACITOR0805"))
    )
    (comp (ref "C43")
      (value "100n")
      (footprint "eagle-import:0402")
      (fields (field (name "MFG") "Murata"))
      (libsource (lib "eagle-import") (part "CAPACITOR0402"))
    )
    (comp (ref "C44")
      (value "10n")
      (footprint "eagle-import:0402")
      (fields (field (name "MFG") "Samsung"))
      (libsource (lib "eagle-import") (part "CAPACITOR0402"))
    )
    (comp (ref "C45")
      (value "10u")
      (footprint "eagle-import:0805")
      (fields (field (name "MFG") "Samsung"))
      (libsource (lib "eagle-import") (part "CAPACITOR0805"))
    )
    (comp (ref "C46")
      (value "100n")
      (footprint "eagle-import:0402")
      (fields (field (name "MFG") "Murata"))
      (libsource (lib "eagle-import") (part "CAPACITOR0402"))
    )
    (comp (ref "LED1")
      (value "LED")
      (footprint "eagle-import:LED-0603")
      (fields (field (name "MFG") "OSRAM"))
      (libsource (lib "eagle-import") (part "LED"))
    )
    (comp (ref "LED2")
      (value "LED")
      (footprint "eagle-import:LED-0603")
      (fields (field (name "MFG") "OSRAM"))
      (libsource (lib "eagle-import") (part "LED"))
    )
    (comp (ref "LED3")
      (value "LED")
      (footprint "eagle-import:LED-0603")
      (fields (field (name "MFG") "OSRAM"))
      (libsource (lib "eagle-import") (part "LED"))
    )
    (comp (ref "LED4")
      (value "LED")
      (footprint "eagle-import:LED-0603")
      (fields (field (name "MFG") "OSRAM"))
      (libsource (lib "eagle-import") (part "LED"))
    )
    (comp (ref "R12")
      (value "1.8k")
      (footprint "eagle-import:0402")
      (fields (field (name "MFG") "TE Connectivity"))
      (libsource (lib "eagle-import") (part "RESISTOR0402"))
    )
    (comp (ref "R13")
      (value "1.8k")
      (footprint "eagle-import:0402")
      (fields (field (name "MFG") "TE Connectivity"))
      (libsource (lib "eagle-import") (part "RESISTOR0402"))
    )
    (comp (ref "R14")
      (value "1.8k")
      (footprint "eagle-import:0402")
      (fields (field (name "MFG") "TE Connectivity"))
      (libsource (lib "eagle-import") (part "RESISTOR0402"))
    )
    (comp (ref "R15")
      (value "1.8k")
      (footprint "eagle-import:0402")
      (fields (field (name "MFG") "TE Connectivity"))
      (libsource (lib "eagle-import") (part "RESISTOR0402"))
    )
    (comp (ref "R16")
      (value "100")
      (footprint "eagle-import:0402")
      (fields (field (name "MFG") "Bourns"))
      (libsource (lib "eagle-import") (part "RESISTOR0402"))
    )
    (comp (ref "R17")
      (value "100")
      (footprint "eagle-import:0402")
      (fields (field (name "MFG") "Bourns"))
      (libsource (lib "eagle-import") (part "RESISTOR0402"))
    )
    (comp (ref "R18")
      (value "10k")
      (footprint "eagle-import:0402")
      (fields (field (name "MFG") "Yageo"))
      (libsource (lib "eagle-import") (part "RESISTOR0402"))
    )
    (comp (ref "R19")
      (value "10k")
      (footprint "eagle-import:0402")
      (fields (field (name "MFG") "Yageo"))
      (libsource (lib "eagle-import") (part "RESISTOR0402"))
    )
    (comp (ref "TP2")
      (value "TEST-POINT")
      (footprint "eagle-import:TEST-POINT")
      (libsource (lib "eagle-import") (part "TEST-POINT"))
    )
    (comp (ref "U15")
      (value "LATTICE-ICE40HX4K-BG121")
      (footprint "eagle-import:LATTICE-ICE40HX4K-BG121")
      (fields (field (name "MFG") "Lattice"))
      (libsource (lib "eagle-import") (part "LATTICE-ICE40HX4K-BG121"))
    )
    (comp (ref "X2")
      (value "SITIME-SIT8021")
      (footprint "eagle-import:SITIME-SIT8021")
      (fields (field (name "MFG") "SiTime") (field (name "PN") "SIT8021AI-J4-18S-16.000000E"))
      (libsource (lib "eagle-import") (part "SITIME-SIT8021"))
    )
    (comp (ref "C65")
      (value "10u")
      (footprint "eagle-import:0805")
      (fields (field (name "MFG") "Samsung"))
      (libsource (lib "eagle-import") (part "CAPACITOR0805"))
    )
    (comp (ref "C66")
      (value "100n")
      (footprint "eagle-import:0402")
      (fields (field (name "MFG") "Murata"))
      (libsource (lib "eagle-import") (part "CAPACITOR0402"))
    )
    (comp (ref "J7")
      (value "MICROSD-SOCKET")
      (footprint "eagle-import:MOLEX-1051620001")
      (fields (field (name "MFG") "Molex"))
      (libsource (lib "eagle-import") (part "MICROSD-SOCKET"))
    )
    (comp (ref "R22")
      (value "47k")
      (footprint "eagle-import:0402")
      (fields (field (name "MFG") "Walsin"))
      (libsource (lib "eagle-import") (part "RESISTOR0402"))
    )
    (comp (ref "R23")
      (value "47k")
      (footprint "eagle-import:0402")
      (fields (field (name "MFG") "Walsin"))
      (libsource (lib "eagle-import") (part "RESISTOR0402"))
    )
    (comp (ref "R24")
      (value "47k")
      (footprint "eagle-import:0402")
      (fields (field (name "MFG") "Walsin"))
      (libsource (lib "eagle-import") (part "RESISTOR0402"))
    )
    (comp (ref "R25")
      (value "47k")
      (footprint "eagle-import:0402")
      (fields (field (name "MFG") "Walsin"))
      (libsource (lib "eagle-import") (part "RESISTOR0402"))
    )
    (comp (ref "R26")
      (value "47k")
      (footprint "eagle-import:0402")
      (fields (field (name "MFG") "Walsin"))
      (libsource (lib "eagle-import") (part "RESISTOR0402"))
    )
  )
  (nets
    (net (code "7") (name "GND") (class "Default")
      (node (ref "C1") (pin "2") (pinfunction "2_2") (pintype "bidirectional"))
      (node (ref "C10") (pin "2") (pinfunction "2_2") (pintype "bidirectional"))
      (node (ref "C11") (pin "2") (pinfunction "2_2") (pintype "bidirectional"))
      (node (ref "C12") (pin "2") (pinfunction "2_2") (pintype "bidirectional"))
      (node (ref "C13") (pin "2") (pinfunction "2_2") (pintype "bidirectional"))
      (node (ref "C14") (pin "2") (pinfunction "2_2") (pintype "bidirectional"))
      (node (ref "C15") (pin "2") (pinfunction "2_2") (pintype "bidirectional"))
      (node (ref "C16") (pin "2") (pinfunction "2_2") (pintype "bidirectional"))
      (node (ref "C17") (pin "2") (pinfunction "2_2") (pintype "bidirectional"))
      (node (ref "C18") (pin "2") (pinfunction "2_2") (pintype "bidirectional"))
      (node (ref "C19") (pin "2") (pinfunction "2_2") (pintype "bidirectional"))
      (node (ref "C2") (pin "2") (pinfunction "2_2") (pintype "bidirectional"))
      (node (ref "C20") (pin "2") (pinfunction "2_2") (pintype "bidirectional"))
      (node (ref "C21") (pin "2") (pinfunction "2_2") (pintype "bidirectional"))
      (node (ref "C22") (pin "2") (pinfunction "2_2") (pintype "bidirectional"))
      (node (ref "C23") (pin "2") (pinfunction "2_2") (pintype "bidirectional"))
      (node (ref "C24") (pin "2") (pinfunction "2_2") (pintype "bidirectional"))
      (node (ref "C25") (pin "2") (pinfunction "2_2") (pintype "bidirectional"))
      (node (ref "C26") (pin "2") (pinfunction "2_2") (pintype "bidirectional"))
      (node (ref "C27") (pin "2") (pinfunction "2_2") (pintype "bidirectional"))
      (node (ref "C28") (pin "2") (pinfunction "2_2") (pintype "bidirectional"))
      (node (ref "C29") (pin "2") (pinfunction "2_2") (pintype "bidirectional"))
      (node (ref "C3") (pin "2") (pinfunction "2_2") (pintype "bidirectional"))
      (node (ref "C30") (pin "2") (pinfunction "2_2") (pintype "bidirectional"))
      (node (ref "C31") (pin "2") (pinfunction "2_2") (pintype "bidirectional"))
      (node (ref "C32") (pin "2") (pinfunction "2_2") (pintype "bidirectional"))
      (node (ref "C33") (pin "2") (pinfunction "2_2") (pintype "bidirectional"))
      (node (ref "C34") (pin "2") (pinfunction "2_2") (pintype "bidirectional"))
      (node (ref "C35") (pin "2") (pinfunction "2_2") (pintype "bidirectional"))
      (node (ref "C36") (pin "2") (pinfunction "2_2") (pintype "bidirectional"))
      (node (ref "C37") (pin "2") (pinfunction "2_2") (pintype "bidirectional"))
      (node (ref "C38") (pin "2") (pinfunction "2_2") (pintype "bidirectional"))
      (node (ref "C39") (pin "2") (pinfunction "2_2") (pintype "bidirectional"))
      (node (ref "C4") (pin "2") (pinfunction "2_2") (pintype "bidirectional"))
      (node (ref "C40") (pin "2") (pinfunction "2_2") (pintype "bidirectional"))
      (node (ref "C41") (pin "2") (pinfunction "2_2") (pintype "bidirectional"))
      (node (ref "C44") (pin "2") (pinfunction "2_2") (pintype "bidirectional"))
      (node (ref "C47") (pin "2") (pinfunction "2_2") (pintype "bidirectional"))
      (node (ref "C48") (pin "2") (pinfunction "2_2") (pintype "bidirectional"))
      (node (ref "C49") (pin "2") (pinfunction "2_2") (pintype "bidirectional"))
      (node (ref "C5") (pin "2") (pinfunction "2_2") (pintype "bidirectional"))
      (node (ref "C50") (pin "2") (pinfunction "2_2") (pintype "bidirectional"))
      (node (ref "C51") (pin "2") (pinfunction "2_2") (pintype "bidirectional"))
      (node (ref "C52") (pin "2") (pinfunction "2_2") (pintype "bidirectional"))
      (node (ref "C53") (pin "2") (pinfunction "2_2") (pintype "bidirectional"))
      (node (ref "C54") (pin "2") (pinfunction "2_2") (pintype "bidirectional"))
      (node (ref "C55") (pin "2") (pinfunction "2_2") (pintype "bidirectional"))
      (node (ref "C56") (pin "2") (pinfunction "2_2") (pintype "bidirectional"))
      (node (ref "C57") (pin "2") (pinfunction "2_2") (pintype "bidirectional"))
      (node (ref "C58") (pin "2") (pinfunction "2_2") (pintype "bidirectional"))
      (node (ref "C59") (pin "2") (pinfunction "2_2") (pintype "bidirectional"))
      (node (ref "C6") (pin "2") (pinfunction "2_2") (pintype "bidirectional"))
      (node (ref "C60") (pin "2") (pinfunction "2_2") (pintype "bidirectional"))
      (node (ref "C61") (pin "2") (pinfunction "2_2") (pintype "bidirectional"))
      (node (ref "C62") (pin "2") (pinfunction "2_2") (pintype "bidirectional"))
      (node (ref "C63") (pin "2") (pinfunction "2_2") (pintype "bidirectional"))
      (node (ref "C64") (pin "2") (pinfunction "2_2") (pintype "bidirectional"))
      (node (ref "C65") (pin "2") (pinfunction "2_2") (pintype "bidirectional"))
      (node (ref "C66") (pin "2") (pinfunction "2_2") (pintype "bidirectional"))
      (node (ref "C67") (pin "2") (pinfunction "2_2") (pintype "bidirectional"))
      (node (ref "C68") (pin "2") (pinfunction "2_2") (pintype "bidirectional"))
      (node (ref "C69") (pin "2") (pinfunction "2_2") (pintype "bidirectional"))
      (node (ref "C7") (pin "2") (pinfunction "2_2") (pintype "bidirectional"))
      (node (ref "C70") (pin "2") (pinfunction "2_2") (pintype "bidirectional"))
      (node (ref "C71") (pin "2") (pinfunction "2_2") (pintype "bidirectional"))
      (node (ref "C72") (pin "2") (pinfunction "2_2") (pintype "bidirectional"))
      (node (ref "C73") (pin "2") (pinfunction "2_2") (pintype "bidirectional"))
      (node (ref "C74") (pin "2") (pinfunction "2_2") (pintype "bidirectional"))
      (node (ref "C75") (pin "2") (pinfunction "2_2") (pintype "bidirectional"))
      (node (ref "C76") (pin "2") (pinfunction "2_2") (pintype "bidirectional"))
      (node (ref "C77") (pin "2") (pinfunction "2_2") (pintype "bidirectional"))
      (node (ref "C78") (pin "2") (pinfunction "2_2") (pintype "bidirectional"))
      (node (ref "C79") (pin "2") (pinfunction "2_2") (pintype "bidirectional"))
      (node (ref "C8") (pin "2") (pinfunction "2_2") (pintype "bidirectional"))
      (node (ref "C80") (pin "2") (pinfunction "2_2") (pintype "bidirectional"))
      (node (ref "C81") (pin "2") (pinfunction "2_2") (pintype "bidirectional"))
      (node (ref "C82") (pin "2") (pinfunction "2_2") (pintype "bidirectional"))
      (node (ref "C83") (pin "2") (pinfunction "2_2") (pintype "bidirectional"))
      (node (ref "C84") (pin "2") (pinfunction "2_2") (pintype "bidirectional"))
      (node (ref "C85") (pin "2") (pinfunction "2_2") (pintype "bidirectional"))
      (node (ref "C86") (pin "2") (pinfunction "2_2") (pintype "bidirectional"))
      (node (ref "C87") (pin "2") (pinfunction "2_2") (pintype "bidirectional"))
      (node (ref "C88") (pin "2") (pinfunction "2_2") (pintype "bidirectional"))
      (node (ref "C9") (pin "2") (pinfunction "2_2") (pintype "bidirectional"))
      (node (ref "H1") (pin "10") (pinfunction "10_10") (pintype "bidirectional"))
      (node (ref "J5") (pin "1") (pinfunction "1_1") (pintype "bidirectional"))
      (node (ref "J5") (pin "2") (pinfunction "2_2") (pintype "bidirectional"))
      (node (ref "J6") (pin "1") (pinfunction "GND1_1") (pintype "bidirectional"))
      (node (ref "J6") (pin "2") (pinfunction "GND2_2") (pintype "bidirectional"))
      (node (ref "J7") (pin "GND1") (pinfunction "GND_GND1") (pintype "bidirectional"))
      (node (ref "J7") (pin "GND2") (pinfunction "GND_GND2") (pintype "bidirectional"))
      (node (ref "J7") (pin "GND3") (pinfunction "GND_GND3") (pintype "bidirectional"))
      (node (ref "J7") (pin "GND4") (pinfunction "GND_GND4") (pintype "bidirectional"))
      (node (ref "J7") (pin "VSS") (pinfunction "GND_VSS") (pintype "bidirectional"))
      (node (ref "J8") (pin "GND") (pinfunction "GND_GND") (pintype "bidirectional"))
      (node (ref "J8") (pin "GND2") (pinfunction "GND_GND2") (pintype "bidirectional"))
      (node (ref "J8") (pin "GND3") (pinfunction "GND_GND3") (pintype "bidirectional"))
      (node (ref "J8") (pin "GND4") (pinfunction "GND_GND4") (pintype "bidirectional"))
      (node (ref "J8") (pin "GND5") (pinfunction "GND_GND5") (pintype "bidirectional"))
      (node (ref "R10") (pin "1") (pinfunction "1_1") (pintype "bidirectional"))
      (node (ref "R12") (pin "2") (pinfunction "2_2") (pintype "bidirectional"))
      (node (ref "R13") (pin "2") (pinfunction "2_2") (pintype "bidirectional"))
      (node (ref "R14") (pin "2") (pinfunction "2_2") (pintype "bidirectional"))
      (node (ref "R15") (pin "2") (pinfunction "2_2") (pintype "bidirectional"))
      (node (ref "R2") (pin "1") (pinfunction "1_1") (pintype "bidirectional"))
      (node (ref "R27") (pin "2") (pinfunction "2_2") (pintype "bidirectional"))
      (node (ref "R28") (pin "2") (pinfunction "2_2") (pintype "bidirectional"))
      (node (ref "R29") (pin "2") (pinfunction "2_2") (pintype "bidirectional"))
      (node (ref "R30") (pin "2") (pinfunction "2_2") (pintype "bidirectional"))
      (node (ref "R31") (pin "1") (pinfunction "1_1") (pintype "bidirectional"))
      (node (ref "R32") (pin "1") (pinfunction "1_1") (pintype "bidirectional"))
      (node (ref "R7") (pin "1") (pinfunction "1_1") (pintype "bidirectional"))
      (node (ref "U1") (pin "B2") (pinfunction "GND_B2") (pintype "bidirectional"))
      (node (ref "U10") (pin "2") (pinfunction "GND_2") (pintype "bidirectional"))
      (node (ref "U11") (pin "2") (pinfunction "GND_2") (pintype "bidirectional"))
      (node (ref "U12") (pin "21") (pinfunction "GND_THERMALPAD_21") (pintype "bidirectional"))
      (node (ref "U12") (pin "6") (pinfunction "GND_6") (pintype "bidirectional"))
      (node (ref "U13") (pin "7") (pinfunction "EN__7") (pintype "bidirectional"))
      (node (ref "U13") (pin "8") (pinfunction "GND_8") (pintype "bidirectional"))
      (node (ref "U14") (pin "3") (pinfunction "GND_3") (pintype "bidirectional"))
      (node (ref "U15") (pin "E5") (pinfunction "GND_E5_E5") (pintype "bidirectional"))
      (node (ref "U15") (pin "E6") (pinfunction "GND_E6_E6") (pintype "bidirectional"))
      (node (ref "U15") (pin "E7") (pinfunction "GND_E7_E7") (pintype "bidirectional"))
      (node (ref "U15") (pin "F5") (pinfunction "GND_F5_F5") (pintype "bidirectional"))
      (node (ref "U15") (pin "F6") (pinfunction "GND_F6_F6") (pintype "bidirectional"))
      (node (ref "U15") (pin "F7") (pinfunction "GND_F7_F7") (pintype "bidirectional"))
      (node (ref "U15") (pin "G5") (pinfunction "GND_G5_G5") (pintype "bidirectional"))
      (node (ref "U15") (pin "G6") (pinfunction "GND_G6_G6") (pintype "bidirectional"))
      (node (ref "U15") (pin "G7") (pinfunction "GND_G7_G7") (pintype "bidirectional"))
      (node (ref "U15") (pin "H5") (pinfunction "GND_H5_H5") (pintype "bidirectional"))
      (node (ref "U16") (pin "3") (pinfunction "GND_3") (pintype "bidirectional"))
      (node (ref "U17") (pin "A3") (pinfunction "AGND_A3") (pintype "bidirectional"))
      (node (ref "U17") (pin "B4") (pinfunction "DGND_B4") (pintype "bidirectional"))
      (node (ref "U17") (pin "B5") (pinfunction "AGND_B5") (pintype "bidirectional"))
      (node (ref "U17") (pin "B6") (pinfunction "DGND_B6") (pintype "bidirectional"))
      (node (ref "U17") (pin "B7") (pinfunction "TEST_B7") (pintype "bidirectional"))
      (node (ref "U17") (pin "C1") (pinfunction "SADDR_C1") (pintype "bidirectional"))
      (node (ref "U17") (pin "C4") (pinfunction "DGND_C4") (pintype "bidirectional"))
      (node (ref "U17") (pin "C5") (pinfunction "DGND_C5") (pintype "bidirectional"))
      (node (ref "U17") (pin "C6") (pinfunction "DGND_C6") (pintype "bidirectional"))
      (node (ref "U17") (pin "D4") (pinfunction "DGND_D4") (pintype "bidirectional"))
      (node (ref "U17") (pin "E6") (pinfunction "DGND_E6") (pintype "bidirectional"))
      (node (ref "U17") (pin "G1") (pinfunction "DGND_G1") (pintype "bidirectional"))
      (node (ref "U17") (pin "H2") (pinfunction "DGND_H2") (pintype "bidirectional"))
      (node (ref "U17") (pin "H3") (pinfunction "DGND_H3") (pintype "bidirectional"))
      (node (ref "U18") (pin "A1") (pinfunction "VSS_A1_A1") (pintype "bidirectional"))
      (node (ref "U18") (pin "A3") (pinfunction "VSSQ_A3_A3") (pintype "bidirectional"))
      (node (ref "U18") (pin "B7") (pinfunction "VSSQ_B7_B7") (pintype "bidirectional"))
      (node (ref "U18") (pin "C3") (pinfunction "VSSQ_C3_C3") (pintype "bidirectional"))
      (node (ref "U18") (pin "D7") (pinfunction "VSSQ_D7_D7") (pintype "bidirectional"))
      (node (ref "U18") (pin "E3") (pinfunction "VSS_E3_E3") (pintype "bidirectional"))
      (node (ref "U18") (pin "J1") (pinfunction "VSS_J1_J1") (pintype "bidirectional"))
      (node (ref "U19") (pin "D5") (pinfunction "VSS_D5_D5") (pintype "bidirectional"))
      (node (ref "U19") (pin "D7") (pinfunction "VSS_D7_D7") (pintype "bidirectional"))
      (node (ref "U19") (pin "D8") (pinfunction "VSS_D8_D8") (pintype "bidirectional"))
      (node (ref "U19") (pin "D9") (pinfunction "VSS_D9_D9") (pintype "bidirectional"))
      (node (ref "U19") (pin "F10") (pinfunction "VSS_F10_F10") (pintype "bidirectional"))
      (node (ref "U19") (pin "F12") (pinfunction "VSS_F12_F12") (pintype "bidirectional"))
      (node (ref "U19") (pin "F2") (pinfunction "VSS_F2_F2") (pintype "bidirectional"))
      (node (ref "U19") (pin "F6") (pinfunction "VSS_F6_F6") (pintype "bidirectional"))
      (node (ref "U19") (pin "F7") (pinfunction "VSS_F7_F7") (pintype "bidirectional"))
      (node (ref "U19") (pin "F8") (pinfunction "VSS_F8_F8") (pintype "bidirectional"))
      (node (ref "U19") (pin "F9") (pinfunction "VSS_F9_F9") (pintype "bidirectional"))
      (node (ref "U19") (pin "G10") (pinfunction "VSS_G10_G10") (pintype "bidirectional"))
      (node (ref "U19") (pin "G12") (pinfunction "VSS_G12_G12") (pintype "bidirectional"))
      (node (ref "U19") (pin "G2") (pinfunction "VSS_G2_G2") (pintype "bidirectional"))
      (node (ref "U19") (pin "G6") (pinfunction "VSS_G6_G6") (pintype "bidirectional"))
      (node (ref "U19") (pin "G7") (pinfunction "VSS_G7_G7") (pintype "bidirectional"))
      (node (ref "U19") (pin "G8") (pinfunction "VSS_G8_G8") (pintype "bidirectional"))
      (node (ref "U19") (pin "G9") (pinfunction "VSS_G9_G9") (pintype "bidirectional"))
      (node (ref "U19") (pin "H10") (pinfunction "VSS_H10_H10") (pintype "bidirectional"))
      (node (ref "U19") (pin "H12") (pinfunction "VSS_H12_H12") (pintype "bidirectional"))
      (node (ref "U19") (pin "H6") (pinfunction "VSS_H6_H6") (pintype "bidirectional"))
      (node (ref "U19") (pin "H7") (pinfunction "VSS_H7_H7") (pintype "bidirectional"))
      (node (ref "U19") (pin "H8") (pinfunction "VSS_H8_H8") (pintype "bidirectional"))
      (node (ref "U19") (pin "H9") (pinfunction "VSS_H9_H9") (pintype "bidirectional"))
      (node (ref "U19") (pin "J10") (pinfunction "VSS_J10_J10") (pintype "bidirectional"))
      (node (ref "U19") (pin "J6") (pinfunction "VSS_J6_J6") (pintype "bidirectional"))
      (node (ref "U19") (pin "J7") (pinfunction "VSS_J7_J7") (pintype "bidirectional"))
      (node (ref "U19") (pin "J8") (pinfunction "VSS_J8_J8") (pintype "bidirectional"))
      (node (ref "U19") (pin "J9") (pinfunction "VSS_J9_J9") (pintype "bidirectional"))
      (node (ref "U19") (pin "K10") (pinfunction "VSS_K10_K10") (pintype "bidirectional"))
      (node (ref "U19") (pin "K6") (pinfunction "VSS_K6_K6") (pintype "bidirectional"))
      (node (ref "U19") (pin "K7") (pinfunction "VSS_K7_K7") (pintype "bidirectional"))
      (node (ref "U19") (pin "K8") (pinfunction "VSS_K8_K8") (pintype "bidirectional"))
      (node (ref "U19") (pin "K9") (pinfunction "VSS_K9_K9") (pintype "bidirectional"))
      (node (ref "U19") (pin "L4") (pinfunction "BYPASS_REG_L4_L4") (pintype "bidirectional"))
      (node (ref "U19") (pin "M1") (pinfunction "VSSA_M1_M1") (pintype "bidirectional"))
      (node (ref "U19") (pin "M8") (pinfunction "VSS_M8_M8") (pintype "bidirectional"))
      (node (ref "U19") (pin "M9") (pinfunction "VSS_M9_M9") (pintype "bidirectional"))
      (node (ref "U19") (pin "N1") (pinfunction "VREF-_N1_N1") (pintype "bidirectional"))
      (node (ref "U2") (pin "2") (pinfunction "GND_2") (pintype "bidirectional"))
      (node (ref "U20") (pin "2") (pinfunction "GND_2") (pintype "bidirectional"))
      (node (ref "U3") (pin "A1") (pinfunction "GND_A1") (pintype "bidirectional"))
      (node (ref "U3") (pin "C1") (pinfunction "MODE_C1") (pintype "bidirectional"))
      (node (ref "U4") (pin "A1") (pinfunction "GND_A1") (pintype "bidirectional"))
      (node (ref "U5") (pin "B1") (pinfunction "MODE_B1") (pintype "bidirectional"))
      (node (ref "U5") (pin "C1") (pinfunction "AGND_C1") (pintype "bidirectional"))
      (node (ref "U5") (pin "C2") (pinfunction "GND_C2") (pintype "bidirectional"))
      (node (ref "U5") (pin "C3") (pinfunction "GND_C3") (pintype "bidirectional"))
      (node (ref "U6") (pin "2") (pinfunction "GND_2") (pintype "bidirectional"))
      (node (ref "U7") (pin "2") (pinfunction "GND_2") (pintype "bidirectional"))
      (node (ref "U8") (pin "2") (pinfunction "GND_2") (pintype "bidirectional"))
      (node (ref "U9") (pin "2") (pinfunction "GND_2") (pintype "bidirectional"))
      (node (ref "X2") (pin "1") (pinfunction "EN__1") (pintype "input"))
      (node (ref "X2") (pin "4") (pinfunction "GND_4") (pintype "bidirectional"))
      (node (ref "X3") (pin "1") (pinfunction "EN__1") (pintype "input"))
      (node (ref "X3") (pin "4") (pinfunction "GND_4") (pintype "bidirectional"))
    )
    (net (code "8") (name "GNDPLL0") (class "Default")
      (node (ref "C45") (pin "2") (pinfunction "2_2") (pintype "bidirectional"))
      (node (ref "C46") (pin "2") (pinfunction "2_2") (pintype "bidirectional"))
      (node (ref "U15") (pin "L6") (pinfunction "GNDPLL0_L6_L6") (pintype "bidirectional"))
    )
    (net (code "9") (name "GNDPLL1") (class "Default")
      (node (ref "C42") (pin "2") (pinfunction "2_2") (pintype "bidirectional"))
      (node (ref "C43") (pin "2") (pinfunction "2_2") (pintype "bidirectional"))
      (node (ref "U15") (pin "C5") (pinfunction "GNDPLL1_C5_C5") (pintype "bidirectional"))
    )
    (net (code "10") (name "ICE_CDONE") (class "Default")
      (node (ref "R18") (pin "2") (pinfunction "2_2") (pintype "bidirectional"))
      (node (ref "U15") (pin "K8") (pinfunction "CDONE_K8_K8") (pintype "bidirectional"))
      (node (ref "U19") (pin "C2") (pinfunction "PI7_C2_C2") (pintype "bidirectional"))
    )
    (net (code "11") (name "ICE_CRST_") (class "Default")
      (node (ref "R19") (pin "2") (pinfunction "2_2") (pintype "bidirectional"))
      (node (ref "U15") (pin "L9") (pinfunction "CRESET_B_L9_L9") (pintype "bidirectional"))
      (node (ref "U19") (pin "C3") (pinfunction "PI6_C3_C3") (pintype "bidirectional"))
    )
    (net (code "12") (name "ICE_IMG_CLK16MHZ") (class "Default")
      (node (ref "TP2") (pin "X") (pinfunction "X_X") (pintype "bidirectional"))
      (node (ref "U15") (pin "C11") (pinfunction "C11_C11") (pintype "bidirectional"))
      (node (ref "U16") (pin "2") (pinfunction "IN_2") (pintype "bidirectional"))
      (node (ref "X2") (pin "2") (pinfunction "OUT_2") (pintype "bidirectional"))
    )
    (net (code "13") (name "ICE_LED0") (class "Default")
      (node (ref "LED4") (pin "A") (pinfunction "A_A") (pintype "bidirectional"))
      (node (ref "U15") (pin "C9") (pinfunction "C9_C9") (pintype "bidirectional"))
    )
    (net (code "14") (name "ICE_LED1") (class "Default")
      (node (ref "LED3") (pin "A") (pinfunction "A_A") (pintype "bidirectional"))
      (node (ref "U15") (pin "A10") (pinfunction "A10_A10") (pintype "bidirectional"))
    )
    (net (code "15") (name "ICE_LED2") (class "Default")
      (node (ref "LED2") (pin "A") (pinfunction "A_A") (pintype "bidirectional"))
      (node (ref "U15") (pin "A11") (pinfunction "A11_A11") (pintype "bidirectional"))
    )
    (net (code "16") (name "ICE_LED3") (class "Default")
      (node (ref "LED1") (pin "A") (pinfunction "A_A") (pintype "bidirectional"))
      (node (ref "U15") (pin "B11") (pinfunction "B11_B11") (pintype "bidirectional"))
    )
    (net (code "17") (name "ICE_MSP_SPI_AUX") (class "Default")
      (node (ref "U13") (pin "10") (pinfunction "B3_10") (pintype "bidirectional"))
      (node (ref "U15") (pin "K3") (pinfunction "K3_K3") (pintype "bidirectional"))
    )
    (net (code "18") (name "ICE_MSP_SPI_AUX_DIR") (class "Default")
      (node (ref "U12") (pin "13") (pinfunction "PA.A/P2.2/TA1.1/A4_13") (pintype "bidirectional"))
      (node (ref "U13") (pin "5") (pinfunction "DIR3_5") (pintype "bidirectional"))
    )
    (net (code "19") (name "ICE_MSP_SPI_AUX_X") (class "Default")
      (node (ref "U12") (pin "14") (pinfunction "PA.7/P1.7/UCA0STE/TDO_14") (pintype "bidirectional"))
      (node (ref "U13") (pin "3") (pinfunction "A3_3") (pintype "bidirectional"))
    )
    (net (code "20") (name "ICE_MSP_SPI_CLK") (class "Default")
      (node (ref "U13") (pin "11") (pinfunction "B2_11") (pintype "bidirectional"))
      (node (ref "U15") (pin "K2") (pinfunction "K2_K2") (pintype "bidirectional"))
    )
    (net (code "21") (name "ICE_MSP_SPI_CLK_X") (class "Default")
      (node (ref "U12") (pin "15") (pinfunction "PA.6/P1.6/UCA0CLK/TA0CLK/TDI/TCLK_15") (pintype "bidirectional"))
      (node (ref "U13") (pin "2") (pinfunction "A2_2") (pintype "bidirectional"))
    )
    (net (code "22") (name "ICE_MSP_SPI_DATA") (class "Default")
      (node (ref "U13") (pin "12") (pinfunction "B1_12") (pintype "bidirectional"))
      (node (ref "U15") (pin "K1") (pinfunction "K1_K1") (pintype "bidirectional"))
    )
    (net (code "23") (name "ICE_MSP_SPI_DATA_DIR") (class "Default")
      (node (ref "U12") (pin "19") (pinfunction "PA.3/P1.3/UCB0SOMI/UCB0SCL/MCLK/A3_19") (pintype "bidirectional"))
      (node (ref "U13") (pin "15") (pinfunction "DIR1_15") (pintype "bidirectional"))
    )
    (net (code "24") (name "ICE_MSP_SPI_DATA_X") (class "Default")
      (node (ref "U12") (pin "16") (pinfunction "PA.5/P1.5/UCA0RXD/UCA0SOMI/TA0.2/TMS_16") (pintype "bidirectional"))
      (node (ref "U12") (pin "17") (pinfunction "PA.4/P1.4/UCA0TXD/UCA0SIMO/TA0.1/TCK_17") (pintype "bidirectional"))
      (node (ref "U13") (pin "1") (pinfunction "A1_1") (pintype "bidirectional"))
    )
    (net (code "25") (name "ICE_ST_SPI_CLK") (class "Default")
      (node (ref "U15") (pin "L10") (pinfunction "SPI_SCK_L10_L10") (pintype "bidirectional"))
      (node (ref "U19") (pin "M6") (pinfunction "PB2_M6_M6") (pintype "bidirectional"))
    )
    (net (code "26") (name "ICE_ST_SPI_CS_") (class "Default")
      (node (ref "U15") (pin "K10") (pinfunction "SPI_SS_B_K10_K10") (pintype "bidirectional"))
      (node (ref "U19") (pin "B6") (pinfunction "PB6_B6_B6") (pintype "bidirectional"))
    )
    (net (code "27") (name "ICE_ST_SPI_D0") (class "Default")
      (node (ref "U15") (pin "J9") (pinfunction "SPI_SI_J9_J9") (pintype "bidirectional"))
      (node (ref "U19") (pin "F14") (pinfunction "PC9_F14_F14") (pintype "bidirectional"))
    )
    (net (code "28") (name "ICE_ST_SPI_D1") (class "Default")
      (node (ref "U15") (pin "K9") (pinfunction "SPI_SO_K9_K9") (pintype "bidirectional"))
      (node (ref "U19") (pin "B14") (pinfunction "PC10_B14_B14") (pintype "bidirectional"))
    )
    (net (code "29") (name "ICE_ST_SPI_D2") (class "Default")
      (node (ref "U15") (pin "L7") (pinfunction "L7_L7") (pintype "bidirectional"))
      (node (ref "U19") (pin "K1") (pinfunction "PF7_K1_K1") (pintype "bidirectional"))
    )
    (net (code "30") (name "ICE_ST_SPI_D3") (class "Default")
      (node (ref "U15") (pin "K6") (pinfunction "K6_K6") (pintype "bidirectional"))
      (node (ref "U19") (pin "K2") (pinfunction "PF6_K2_K2") (pintype "bidirectional"))
    )
    (net (code "31") (name "ICE_ST_SPI_D4") (class "Default")
      (node (ref "U15") (pin "J7") (pinfunction "J7_J7") (pintype "bidirectional"))
      (node (ref "U19") (pin "F4") (pinfunction "PH2_F4_F4") (pintype "bidirectional"))
    )
    (net (code "32") (name "ICE_ST_SPI_D5") (class "Default")
      (node (ref "U15") (pin "K7") (pinfunction "K7_K7") (pintype "bidirectional"))
      (node (ref "U19") (pin "G4") (pinfunction "PH3_G4_G4") (pintype "bidirectional"))
    )
    (net (code "33") (name "ICE_ST_SPI_D6") (class "Default")
      (node (ref "U15") (pin "H7") (pinfunction "H7_H7") (pintype "bidirectional"))
      (node (ref "U19") (pin "C10") (pinfunction "PG9_C10_C10") (pintype "bidirectional"))
    )
    (net (code "34") (name "ICE_ST_SPI_D7") (class "Default")
      (node (ref "U15") (pin "L8") (pinfunction "L8_L8") (pintype "bidirectional"))
      (node (ref "U19") (pin "A7") (pinfunction "PG14_A7_A7") (pintype "bidirectional"))
    )
    (net (code "35") (name "IMG_CLK16MHZ") (class "Default")
      (node (ref "U16") (pin "4") (pinfunction "OUT_4") (pintype "bidirectional"))
      (node (ref "U17") (pin "D7") (pinfunction "EXTCLK_D7") (pintype "bidirectional"))
    )
    (net (code "36") (name "IMG_D0") (class "Default")
      (node (ref "U15") (pin "E8") (pinfunction "E8_E8") (pintype "bidirectional"))
      (node (ref "U17") (pin "G6") (pinfunction "DOUT0_G6") (pintype "bidirectional"))
    )
    (net (code "37") (name "IMG_D1") (class "Default")
      (node (ref "U15") (pin "D10") (pinfunction "D10_D10") (pintype "bidirectional"))
      (node (ref "U17") (pin "G5") (pinfunction "DOUT1_G5") (pintype "bidirectional"))
    )
    (net (code "38") (name "IMG_D2") (class "Default")
      (node (ref "U15") (pin "G11") (pinfunction "G11_G11") (pintype "bidirectional"))
      (node (ref "U17") (pin "H4") (pinfunction "DOUT2_H4") (pintype "bidirectional"))
    )
    (net (code "39") (name "IMG_D3") (class "Default")
      (node (ref "U15") (pin "G9") (pinfunction "G9_G9") (pintype "bidirectional"))
      (node (ref "U17") (pin "G4") (pinfunction "DOUT3_G4") (pintype "bidirectional"))
    )
    (net (code "40") (name "IMG_D4") (class "Default")
      (node (ref "U15") (pin "E9") (pinfunction "E9_E9") (pintype "bidirectional"))
      (node (ref "U17") (pin "F5") (pinfunction "DOUT4_F5") (pintype "bidirectional"))
    )
    (net (code "41") (name "IMG_D5") (class "Default")
      (node (ref "U15") (pin "K11") (pinfunction "K11_K11") (pintype "bidirectional"))
      (node (ref "U17") (pin "G3") (pinfunction "DOUT5_G3") (pintype "bidirectional"))
    )
    (net (code "42") (name "IMG_D6") (class "Default")
      (node (ref "U15") (pin "F9") (pinfunction "F9_F9") (pintype "bidirectional"))
      (node (ref "U17") (pin "F4") (pinfunction "DOUT6_F4") (pintype "bidirectional"))
    )
    (net (code "43") (name "IMG_D7") (class "Default")
      (node (ref "U15") (pin "G8") (pinfunction "G8_G8") (pintype "bidirectional"))
      (node (ref "U17") (pin "E4") (pinfunction "DOUT7_E4") (pintype "bidirectional"))
    )
    (net (code "44") (name "IMG_D8") (class "Default")
      (node (ref "U15") (pin "J10") (pinfunction "J10_J10") (pintype "bidirectional"))
      (node (ref "U17") (pin "F3") (pinfunction "DOUT8_F3") (pintype "bidirectional"))
    )
    (net (code "45") (name "IMG_D9") (class "Default")
      (node (ref "U15") (pin "J11") (pinfunction "J11_J11") (pintype "bidirectional"))
      (node (ref "U17") (pin "E3") (pinfunction "DOUT9_E3") (pintype "bidirectional"))
    )
    (net (code "46") (name "IMG_D10") (class "Default")
      (node (ref "U15") (pin "H11") (pinfunction "H11_H11") (pintype "bidirectional"))
      (node (ref "U17") (pin "D3") (pinfunction "DOUT10_D3") (pintype "bidirectional"))
    )
    (net (code "47") (name "IMG_D11") (class "Default")
      (node (ref "U15") (pin "H10") (pinfunction "H10_H10") (pintype "bidirectional"))
      (node (ref "U17") (pin "E2") (pinfunction "DOUT11_E2") (pintype "bidirectional"))
    )
    (net (code "48") (name "IMG_DCLK") (class "Default")
      (node (ref "U15") (pin "F11") (pinfunction "F11_F11") (pintype "bidirectional"))
      (node (ref "U17") (pin "E1") (pinfunction "PIXCLK_E1") (pintype "bidirectional"))
    )
    (net (code "49") (name "IMG_FV") (class "Default")
      (node (ref "U15") (pin "E11") (pinfunction "E11_E11") (pintype "bidirectional"))
      (node (ref "U17") (pin "B3") (pinfunction "FRAME_VALID_B3") (pintype "bidirectional"))
    )
    (net (code "50") (name "IMG_LV") (class "Default")
      (node (ref "U15") (pin "E10") (pinfunction "E10_E10") (pintype "bidirectional"))
      (node (ref "U17") (pin "C3") (pinfunction "LINE_VALID_C3") (pintype "bidirectional"))
    )
    (net (code "51") (name "IMG_RST_") (class "Default")
      (node (ref "R20") (pin "1") (pinfunction "1_1") (pintype "bidirectional"))
      (node (ref "U15") (pin "D11") (pinfunction "D11_D11") (pintype "bidirectional"))
      (node (ref "U17") (pin "C8") (pinfunction "RST__C8") (pintype "bidirectional"))
    )
    (net (code "52") (name "IMG_SCLK") (class "Default")
      (node (ref "U15") (pin "G10") (pinfunction "G10_G10") (pintype "bidirectional"))
      (node (ref "U17") (pin "D1") (pinfunction "SCLK_D1") (pintype "bidirectional"))
    )
    (net (code "53") (name "IMG_SDATA") (class "Default")
      (node (ref "R21") (pin "2") (pinfunction "2_2") (pintype "bidirectional"))
      (node (ref "U15") (pin "F10") (pinfunction "F10_F10") (pintype "bidirectional"))
      (node (ref "U17") (pin "B2") (pinfunction "SDATA_B2") (pintype "bidirectional"))
    )
    (net (code "54") (name "MOTION_SIGNAL") (class "Default")
      (node (ref "U12") (pin "10") (pinfunction "PA.D/P2.5/UCB0SIMO/UCB0SDA/A7_10") (pintype "bidirectional"))
      (node (ref "U14") (pin "2") (pinfunction "OUT_2") (pintype "bidirectional"))
    )
    (net (code "55") (name "MSP_RST_") (class "Default")
      (node (ref "C26") (pin "1") (pinfunction "1_1") (pintype "bidirectional"))
      (node (ref "R11") (pin "1") (pinfunction "1_1") (pintype "bidirectional"))
      (node (ref "U12") (pin "4") (pinfunction "RST_/NMI/SBWTDIO_4") (pintype "bidirectional"))
      (node (ref "U19") (pin "R5") (pinfunction "PB0_R5_R5") (pintype "bidirectional"))
    )
    (net (code "56") (name "MSP_TEST") (class "Default")
      (node (ref "U12") (pin "3") (pinfunction "TEST/SBWTCK_3") (pintype "bidirectional"))
      (node (ref "U19") (pin "R4") (pinfunction "PB1_R4_R4") (pintype "bidirectional"))
    )
    (net (code "57") (name "Net-(C2-Pad1)") (class "Default")
      (node (ref "C2") (pin "1") (pinfunction "1_1") (pintype "bidirectional"))
      (node (ref "Q1") (pin "4") (pinfunction "S_4") (pintype "bidirectional"))
      (node (ref "Q1") (pin "8") (pinfunction "S_8") (pintype "bidirectional"))
      (node (ref "Q2") (pin "4") (pinfunction "S_4") (pintype "bidirectional"))
      (node (ref "Q2") (pin "8") (pinfunction "S_8") (pintype "bidirectional"))
      (node (ref "Q3") (pin "4") (pinfunction "S_4") (pintype "bidirectional"))
      (node (ref "Q3") (pin "8") (pinfunction "S_8") (pintype "bidirectional"))
      (node (ref "R3") (pin "1") (pinfunction "1_1") (pintype "bidirectional"))
    )
    (net (code "58") (name "Net-(C13-Pad1)") (class "Default")
      (node (ref "C13") (pin "1") (pinfunction "1_1") (pintype "bidirectional"))
      (node (ref "C14") (pin "1") (pinfunction "1_1") (pintype "bidirectional"))
      (node (ref "R8") (pin "2") (pinfunction "2_2") (pintype "bidirectional"))
      (node (ref "R9") (pin "2") (pinfunction "2_2") (pintype "bidirectional"))
      (node (ref "U5") (pin "E2") (pinfunction "VOUT_E2") (pintype "bidirectional"))
      (node (ref "U5") (pin "E3") (pinfunction "VOUT_E3") (pintype "bidirectional"))
    )
    (net (code "59") (name "Net-(D1-C)") (class "Default")
      (node (ref "C3") (pin "1") (pinfunction "1_1") (pintype "bidirectional"))
      (node (ref "D1") (pin "2") (pinfunction "C_2") (pintype "bidirectional"))
      (node (ref "J3") (pin "1") (pinfunction "1_1") (pintype "bidirectional"))
      (node (ref "Q3") (pin "1") (pinfunction "D_1") (pintype "bidirectional"))
      (node (ref "Q3") (pin "2") (pinfunction "D_2") (pintype "bidirectional"))
      (node (ref "Q3") (pin "5") (pinfunction "D_5") (pintype "bidirectional"))
      (node (ref "Q3") (pin "6") (pinfunction "D_6") (pintype "bidirectional"))
      (node (ref "Q3") (pin "7") (pinfunction "D_7") (pintype "bidirectional"))
    )
    (net (code "60") (name "Net-(FB1-P$1)") (class "Default")
      (node (ref "FB1") (pin "1") (pinfunction "P$1_1") (pintype "bidirectional"))
      (node (ref "J8") (pin "VCC") (pinfunction "VCC_VCC") (pintype "bidirectional"))
      (node (ref "U20") (pin "4") (pinfunction "IO3_4") (pintype "bidirectional"))
      (node (ref "U20") (pin "5") (pinfunction "VDD_5") (pintype "bidirectional"))
      (node (ref "U20") (pin "6") (pinfunction "IO4_6") (pintype "bidirectional"))
    )
    (net (code "61") (name "Net-(J2-Pad2)") (class "Default")
      (node (ref "J2") (pin "2") (pinfunction "2_2") (pintype "bidirectional"))
      (node (ref "Q2") (pin "1") (pinfunction "D_1") (pintype "bidirectional"))
      (node (ref "Q2") (pin "2") (pinfunction "D_2") (pintype "bidirectional"))
      (node (ref "Q2") (pin "5") (pinfunction "D_5") (pintype "bidirectional"))
      (node (ref "Q2") (pin "6") (pinfunction "D_6") (pintype "bidirectional"))
      (node (ref "Q2") (pin "7") (pinfunction "D_7") (pintype "bidirectional"))
    )
    (net (code "62") (name "Net-(L3-Pad1)") (class "Default")
      (node (ref "L3") (pin "1") (pinfunction "1_1") (pintype "bidirectional"))
      (node (ref "U5") (pin "B2") (pinfunction "L1_B2") (pintype "bidirectional"))
      (node (ref "U5") (pin "B3") (pinfunction "L1_B3") (pintype "bidirectional"))
    )
    (net (code "63") (name "Net-(L3-Pad2)") (class "Default")
      (node (ref "L3") (pin "2") (pinfunction "2_2") (pintype "bidirectional"))
      (node (ref "U5") (pin "D2") (pinfunction "L2_D2") (pintype "bidirectional"))
      (node (ref "U5") (pin "D3") (pinfunction "L2_D3") (pintype "bidirectional"))
    )
    (net (code "64") (name "Net-(LED1-PadC)") (class "Default")
      (node (ref "LED1") (pin "C") (pinfunction "C_C") (pintype "bidirectional"))
      (node (ref "R12") (pin "1") (pinfunction "1_1") (pintype "bidirectional"))
    )
    (net (code "65") (name "Net-(LED2-PadC)") (class "Default")
      (node (ref "LED2") (pin "C") (pinfunction "C_C") (pintype "bidirectional"))
      (node (ref "R13") (pin "1") (pinfunction "1_1") (pintype "bidirectional"))
    )
    (net (code "66") (name "Net-(LED3-PadC)") (class "Default")
      (node (ref "LED3") (pin "C") (pinfunction "C_C") (pintype "bidirectional"))
      (node (ref "R14") (pin "1") (pinfunction "1_1") (pintype "bidirectional"))
    )
    (net (code "67") (name "Net-(LED4-PadC)") (class "Default")
      (node (ref "LED4") (pin "C") (pinfunction "C_C") (pintype "bidirectional"))
      (node (ref "R15") (pin "1") (pinfunction "1_1") (pintype "bidirectional"))
    )
    (net (code "68") (name "Net-(LED5-PadC)") (class "Default")
      (node (ref "LED5") (pin "C") (pinfunction "C_C") (pintype "bidirectional"))
      (node (ref "R27") (pin "1") (pinfunction "1_1") (pintype "bidirectional"))
    )
    (net (code "69") (name "Net-(LED6-PadC)") (class "Default")
      (node (ref "LED6") (pin "C") (pinfunction "C_C") (pintype "bidirectional"))
      (node (ref "R28") (pin "1") (pinfunction "1_1") (pintype "bidirectional"))
    )
    (net (code "70") (name "Net-(LED7-PadC)") (class "Default")
      (node (ref "LED7") (pin "C") (pinfunction "C_C") (pintype "bidirectional"))
      (node (ref "R29") (pin "1") (pinfunction "1_1") (pintype "bidirectional"))
    )
    (net (code "71") (name "Net-(LED8-PadC)") (class "Default")
      (node (ref "LED8") (pin "C") (pinfunction "C_C") (pintype "bidirectional"))
      (node (ref "R30") (pin "1") (pinfunction "1_1") (pintype "bidirectional"))
    )
    (net (code "72") (name "Net-(Q3-G)") (class "Default")
      (node (ref "Q3") (pin "3") (pinfunction "G_3") (pintype "bidirectional"))
      (node (ref "R3") (pin "2") (pinfunction "2_2") (pintype "bidirectional"))
      (node (ref "R4") (pin "1") (pinfunction "1_1") (pintype "bidirectional"))
    )
    (net (code "73") (name "Net-(U1-VOUT)") (class "Default")
      (node (ref "C1") (pin "1") (pinfunction "1_1") (pintype "bidirectional"))
      (node (ref "J1") (pin "1") (pinfunction "1_1") (pintype "bidirectional"))
      (node (ref "Q1") (pin "1") (pinfunction "D_1") (pintype "bidirectional"))
      (node (ref "Q1") (pin "2") (pinfunction "D_2") (pintype "bidirectional"))
      (node (ref "Q1") (pin "5") (pinfunction "D_5") (pintype "bidirectional"))
      (node (ref "Q1") (pin "6") (pinfunction "D_6") (pintype "bidirectional"))
      (node (ref "Q1") (pin "7") (pinfunction "D_7") (pintype "bidirectional"))
      (node (ref "U1") (pin "A2") (pinfunction "VOUT_A2") (pintype "bidirectional"))
    )
    (net (code "74") (name "Net-(U2-EN)") (class "Default")
      (node (ref "C4") (pin "1") (pinfunction "1_1") (pintype "bidirectional"))
      (node (ref "J4") (pin "2") (pinfunction "2_2") (pintype "bidirectional"))
      (node (ref "U2") (pin "1") (pinfunction "VIN_1") (pintype "bidirectional"))
      (node (ref "U2") (pin "3") (pinfunction "EN_3") (pintype "bidirectional"))
    )
    (net (code "75") (name "Net-(U3-SW)") (class "Default")
      (node (ref "L1") (pin "1") (pinfunction "1_1") (pintype "bidirectional"))
      (node (ref "U3") (pin "B2") (pinfunction "SW_B2") (pintype "bidirectional"))
    )
    (net (code "76") (name "Net-(U3-VOS)") (class "Default")
      (node (ref "C7") (pin "1") (pinfunction "1_1") (pintype "bidirectional"))
      (node (ref "L1") (pin "2") (pinfunction "2_2") (pintype "bidirectional"))
      (node (ref "R5") (pin "2") (pinfunction "2_2") (pintype "bidirectional"))
      (node (ref "U3") (pin "A2") (pinfunction "VOS_A2") (pintype "bidirectional"))
    )
    (net (code "77") (name "Net-(U4-MODE)") (class "Default")
      (node (ref "R7") (pin "2") (pinfunction "2_2") (pintype "bidirectional"))
      (node (ref "U4") (pin "C1") (pinfunction "MODE_C1") (pintype "bidirectional"))
    )
    (net (code "78") (name "Net-(U4-SW)") (class "Default")
      (node (ref "L2") (pin "1") (pinfunction "1_1") (pintype "bidirectional"))
      (node (ref "U4") (pin "B2") (pinfunction "SW_B2") (pintype "bidirectional"))
    )
    (net (code "79") (name "Net-(U4-VOS)") (class "Default")
      (node (ref "C10") (pin "1") (pinfunction "1_1") (pintype "bidirectional"))
      (node (ref "L2") (pin "2") (pinfunction "2_2") (pintype "bidirectional"))
      (node (ref "R6") (pin "2") (pinfunction "2_2") (pintype "bidirectional"))
      (node (ref "U4") (pin "A2") (pinfunction "VOS_A2") (pintype "bidirectional"))
    )
    (net (code "80") (name "Net-(U5-FB)") (class "Default")
      (node (ref "R10") (pin "2") (pinfunction "2_2") (pintype "bidirectional"))
      (node (ref "R9") (pin "1") (pinfunction "1_1") (pintype "bidirectional"))
      (node (ref "U5") (pin "D1") (pinfunction "FB_D1") (pintype "bidirectional"))
    )
    (net (code "81") (name "Net-(U12B-PA.1{slash}P1.1{slash}UCB0CLK{slash}ACLK{slash}A1{slash}VREF+)") (class "Default")
      (node (ref "TP1") (pin "X") (pinfunction "X_X") (pintype "bidirectional"))
      (node (ref "U12") (pin "1") (pinfunction "PA.1/P1.1/UCB0CLK/ACLK/A1/VREF+_1") (pintype "bidirectional"))
    )
    (net (code "82") (name "Net-(U12C-PA.8{slash}P2.0{slash}UCA0TXD{slash}UCA0SIMO{slash}XOUT)") (class "Default")
      (node (ref "C23") (pin "1") (pinfunction "1_1") (pintype "bidirectional"))
      (node (ref "U12") (pin "8") (pinfunction "PA.8/P2.0/UCA0TXD/UCA0SIMO/XOUT_8") (pintype "bidirectional"))
      (node (ref "X1") (pin "4") (pinfunction "B_4") (pintype "bidirectional"))
    )
    (net (code "83") (name "Net-(U12C-PA.9{slash}P2.1{slash}UCA0RXD{slash}UCA0SOMI{slash}XIN)") (class "Default")
      (node (ref "C22") (pin "1") (pinfunction "1_1") (pintype "bidirectional"))
      (node (ref "U12") (pin "7") (pinfunction "PA.9/P2.1/UCA0RXD/UCA0SOMI/XIN_7") (pintype "bidirectional"))
      (node (ref "X1") (pin "1") (pinfunction "A_1") (pintype "bidirectional"))
    )
    (net (code "84") (name "Net-(U19J-OTG_HS_REXT_J15)") (class "Default")
      (node (ref "R32") (pin "2") (pinfunction "2_2") (pintype "bidirectional"))
      (node (ref "U19") (pin "J15") (pinfunction "OTG_HS_REXT_J15_J15") (pintype "bidirectional"))
    )
    (net (code "85") (name "Net-(U19J-VDD12OTGHS_J14)") (class "Default")
      (node (ref "C69") (pin "1") (pinfunction "1_1") (pintype "bidirectional"))
      (node (ref "U19") (pin "J14") (pinfunction "VDD12OTGHS_J14_J14") (pintype "bidirectional"))
    )
    (net (code "86") (name "Net-(U19K-VCAP_1_M10)") (class "Default")
      (node (ref "C86") (pin "1") (pinfunction "1_1") (pintype "bidirectional"))
      (node (ref "U19") (pin "M10") (pinfunction "VCAP_1_M10_M10") (pintype "bidirectional"))
    )
    (net (code "87") (name "Net-(U19K-VCAP_2_F13)") (class "Default")
      (node (ref "C87") (pin "1") (pinfunction "1_1") (pintype "bidirectional"))
      (node (ref "U19") (pin "F13") (pinfunction "VCAP_2_F13_F13") (pintype "bidirectional"))
    )
    (net (code "88") (name "RAM_A0") (class "Default")
      (node (ref "U15") (pin "D5") (pinfunction "D5_D5") (pintype "bidirectional"))
      (node (ref "U18") (pin "H7") (pinfunction "A0_H7") (pintype "bidirectional"))
    )
    (net (code "89") (name "RAM_A1") (class "Default")
      (node (ref "U15") (pin "B3") (pinfunction "B3_B3") (pintype "bidirectional"))
      (node (ref "U18") (pin "H8") (pinfunction "A1_H8") (pintype "bidirectional"))
    )
    (net (code "90") (name "RAM_A2") (class "Default")
      (node (ref "U15") (pin "B2") (pinfunction "B2_B2") (pintype "bidirectional"))
      (node (ref "U18") (pin "J8") (pinfunction "A2_J8") (pintype "bidirectional"))
    )
    (net (code "91") (name "RAM_A3") (class "Default")
      (node (ref "U15") (pin "A1") (pinfunction "A1_A1") (pintype "bidirectional"))
      (node (ref "U18") (pin "J7") (pinfunction "A3_J7") (pintype "bidirectional"))
    )
    (net (code "92") (name "RAM_A4") (class "Default")
      (node (ref "U15") (pin "B1") (pinfunction "B1_B1") (pintype "bidirectional"))
      (node (ref "U18") (pin "J3") (pinfunction "A4_J3") (pintype "bidirectional"))
    )
    (net (code "93") (name "RAM_A5") (class "Default")
      (node (ref "U15") (pin "C2") (pinfunction "C2_C2") (pintype "bidirectional"))
      (node (ref "U18") (pin "J2") (pinfunction "A5_J2") (pintype "bidirectional"))
    )
    (net (code "94") (name "RAM_A6") (class "Default")
      (node (ref "U15") (pin "C4") (pinfunction "C4_C4") (pintype "bidirectional"))
      (node (ref "U18") (pin "H3") (pinfunction "A6_H3") (pintype "bidirectional"))
    )
    (net (code "95") (name "RAM_A7") (class "Default")
      (node (ref "U15") (pin "D2") (pinfunction "D2_D2") (pintype "bidirectional"))
      (node (ref "U18") (pin "H2") (pinfunction "A7_H2") (pintype "bidirectional"))
    )
    (net (code "96") (name "RAM_A8") (class "Default")
      (node (ref "U15") (pin "C1") (pinfunction "C1_C1") (pintype "bidirectional"))
      (node (ref "U18") (pin "H1") (pinfunction "A8_H1") (pintype "bidirectional"))
    )
    (net (code "97") (name "RAM_A9") (class "Default")
      (node (ref "U15") (pin "C3") (pinfunction "C3_C3") (pintype "bidirectional"))
      (node (ref "U18") (pin "G3") (pinfunction "A9_G3") (pintype "bidirectional"))
    )
    (net (code "98") (name "RAM_A10") (class "Default")
      (node (ref "U15") (pin "A2") (pinfunction "A2_A2") (pintype "bidirectional"))
      (node (ref "U18") (pin "H9") (pinfunction "A10_H9") (pintype "bidirectional"))
    )
    (net (code "99") (name "RAM_A11") (class "Default")
      (node (ref "U15") (pin "D1") (pinfunction "D1_D1") (pintype "bidirectional"))
      (node (ref "U18") (pin "G2") (pinfunction "A11_G2") (pintype "bidirectional"))
    )
    (net (code "100") (name "RAM_BA0") (class "Default")
      (node (ref "U15") (pin "C7") (pinfunction "C7_C7") (pintype "bidirectional"))
      (node (ref "U18") (pin "G7") (pinfunction "BA0_G7") (pintype "bidirectional"))
    )
    (net (code "101") (name "RAM_BA1") (class "Default")
      (node (ref "U15") (pin "B4") (pinfunction "B4_B4") (pintype "bidirectional"))
      (node (ref "U18") (pin "G8") (pinfunction "BA1_G8") (pintype "bidirectional"))
    )
    (net (code "102") (name "RAM_CAS_") (class "Default")
      (node (ref "U15") (pin "D7") (pinfunction "D7_D7") (pintype "bidirectional"))
      (node (ref "U18") (pin "F7") (pinfunction "~{CAS}_F7") (pintype "bidirectional"))
    )
    (net (code "103") (name "RAM_CKE") (class "Default")
      (node (ref "U15") (pin "D3") (pinfunction "D3_D3") (pintype "bidirectional"))
      (node (ref "U18") (pin "F3") (pinfunction "CKE_F3") (pintype "bidirectional"))
    )
    (net (code "104") (name "RAM_CLK") (class "Default")
      (node (ref "U15") (pin "E1") (pinfunction "E1_E1") (pintype "bidirectional"))
      (node (ref "U18") (pin "F2") (pinfunction "CLK_F2") (pintype "bidirectional"))
    )
    (net (code "105") (name "RAM_CS_") (class "Default")
      (node (ref "U15") (pin "A3") (pinfunction "A3_A3") (pintype "bidirectional"))
      (node (ref "U18") (pin "G9") (pinfunction "~{CS}_G9") (pintype "bidirectional"))
    )
    (net (code "106") (name "RAM_DQ0") (class "Default")
      (node (ref "U15") (pin "A9") (pinfunction "A9_A9") (pintype "bidirectional"))
      (node (ref "U18") (pin "A8") (pinfunction "DQ0_A8") (pintype "bidirectional"))
    )
    (net (code "107") (name "RAM_DQ1") (class "Default")
      (node (ref "U15") (pin "A8") (pinfunction "A8_A8") (pintype "bidirectional"))
      (node (ref "U18") (pin "B9") (pinfunction "DQ1_B9") (pintype "bidirectional"))
    )
    (net (code "108") (name "RAM_DQ2") (class "Default")
      (node (ref "U15") (pin "B9") (pinfunction "B9_B9") (pintype "bidirectional"))
      (node (ref "U18") (pin "B8") (pinfunction "DQ2_B8") (pintype "bidirectional"))
    )
    (net (code "109") (name "RAM_DQ3") (class "Default")
      (node (ref "U15") (pin "A7") (pinfunction "A7_A7") (pintype "bidirectional"))
      (node (ref "U18") (pin "C9") (pinfunction "DQ3_C9") (pintype "bidirectional"))
    )
    (net (code "110") (name "RAM_DQ4") (class "Default")
      (node (ref "U15") (pin "B8") (pinfunction "B8_B8") (pintype "bidirectional"))
      (node (ref "U18") (pin "C8") (pinfunction "DQ4_C8") (pintype "bidirectional"))
    )
    (net (code "111") (name "RAM_DQ5") (class "Default")
      (node (ref "U15") (pin "A6") (pinfunction "A6_A6") (pintype "bidirectional"))
      (node (ref "U18") (pin "D9") (pinfunction "DQ5_D9") (pintype "bidirectional"))
    )
    (net (code "112") (name "RAM_DQ6") (class "Default")
      (node (ref "U15") (pin "B7") (pinfunction "B7_B7") (pintype "bidirectional"))
      (node (ref "U18") (pin "D8") (pinfunction "DQ6_D8") (pintype "bidirectional"))
    )
    (net (code "113") (name "RAM_DQ7") (class "Default")
      (node (ref "U15") (pin "A5") (pinfunction "A5_A5") (pintype "bidirectional"))
      (node (ref "U18") (pin "E9") (pinfunction "DQ7_E9") (pintype "bidirectional"))
    )
    (net (code "114") (name "RAM_DQ8") (class "Default")
      (node (ref "U15") (pin "F2") (pinfunction "F2_F2") (pintype "bidirectional"))
      (node (ref "U18") (pin "E1") (pinfunction "DQ8_E1") (pintype "bidirectional"))
    )
    (net (code "115") (name "RAM_DQ9") (class "Default")
      (node (ref "U15") (pin "G2") (pinfunction "G2_G2") (pintype "bidirectional"))
      (node (ref "U18") (pin "D2") (pinfunction "DQ9_D2") (pintype "bidirectional"))
    )
    (net (code "116") (name "RAM_DQ10") (class "Default")
      (node (ref "U15") (pin "F1") (pinfunction "F1_F1") (pintype "bidirectional"))
      (node (ref "U18") (pin "D1") (pinfunction "DQ10_D1") (pintype "bidirectional"))
    )
    (net (code "117") (name "RAM_DQ11") (class "Default")
      (node (ref "U15") (pin "H2") (pinfunction "H2_H2") (pintype "bidirectional"))
      (node (ref "U18") (pin "C2") (pinfunction "DQ11_C2") (pintype "bidirectional"))
    )
    (net (code "118") (name "RAM_DQ12") (class "Default")
      (node (ref "U15") (pin "G1") (pinfunction "G1_G1") (pintype "bidirectional"))
      (node (ref "U18") (pin "C1") (pinfunction "DQ12_C1") (pintype "bidirectional"))
    )
    (net (code "119") (name "RAM_DQ13") (class "Default")
      (node (ref "U15") (pin "J2") (pinfunction "J2_J2") (pintype "bidirectional"))
      (node (ref "U18") (pin "B2") (pinfunction "DQ13_B2") (pintype "bidirectional"))
    )
    (net (code "120") (name "RAM_DQ14") (class "Default")
      (node (ref "U15") (pin "H1") (pinfunction "H1_H1") (pintype "bidirectional"))
      (node (ref "U18") (pin "B1") (pinfunction "DQ14_B1") (pintype "bidirectional"))
    )
    (net (code "121") (name "RAM_DQ15") (class "Default")
      (node (ref "U15") (pin "J1") (pinfunction "J1_J1") (pintype "bidirectional"))
      (node (ref "U18") (pin "A2") (pinfunction "DQ15_A2") (pintype "bidirectional"))
    )
    (net (code "122") (name "RAM_DQM0") (class "Default")
      (node (ref "U15") (pin "B6") (pinfunction "B6_B6") (pintype "bidirectional"))
      (node (ref "U18") (pin "E8") (pinfunction "LDQM_E8") (pintype "bidirectional"))
    )
    (net (code "123") (name "RAM_DQM1") (class "Default")
      (node (ref "U15") (pin "E2") (pinfunction "E2_E2") (pintype "bidirectional"))
      (node (ref "U18") (pin "F1") (pinfunction "UDQM_F1") (pintype "bidirectional"))
    )
    (net (code "124") (name "RAM_RAS_") (class "Default")
      (node (ref "U15") (pin "B5") (pinfunction "B5_B5") (pintype "bidirectional"))
      (node (ref "U18") (pin "F8") (pinfunction "~{RAS}_F8") (pintype "bidirectional"))
    )
    (net (code "125") (name "RAM_WE_") (class "Default")
      (node (ref "U15") (pin "A4") (pinfunction "A4_A4") (pintype "bidirectional"))
      (node (ref "U18") (pin "F9") (pinfunction "~{WE}_F9") (pintype "bidirectional"))
    )
    (net (code "126") (name "SD_CLK") (class "Default")
      (node (ref "J7") (pin "CLK") (pinfunction "CLK_CLK") (pintype "bidirectional"))
      (node (ref "U15") (pin "K4") (pinfunction "K4_K4") (pintype "bidirectional"))
    )
    (net (code "127") (name "SD_CMD") (class "Default")
      (node (ref "J7") (pin "CMD") (pinfunction "CMD_CMD") (pintype "bidirectional"))
      (node (ref "R22") (pin "1") (pinfunction "1_1") (pintype "bidirectional"))
      (node (ref "U15") (pin "L3") (pinfunction "L3_L3") (pintype "bidirectional"))
    )
    (net (code "128") (name "SD_DAT0") (class "Default")
      (node (ref "J7") (pin "DAT0") (pinfunction "DAT0_DAT0") (pintype "bidirectional"))
      (node (ref "R23") (pin "1") (pinfunction "1_1") (pintype "bidirectional"))
      (node (ref "U15") (pin "L4") (pinfunction "L4_L4") (pintype "bidirectional"))
    )
    (net (code "129") (name "SD_DAT1") (class "Default")
      (node (ref "J7") (pin "DAT1") (pinfunction "DAT1_DAT1") (pintype "bidirectional"))
      (node (ref "R24") (pin "1") (pinfunction "1_1") (pintype "bidirectional"))
      (node (ref "U15") (pin "K5") (pinfunction "K5_K5") (pintype "bidirectional"))
    )
    (net (code "130") (name "SD_DAT2") (class "Default")
      (node (ref "J7") (pin "DAT2") (pinfunction "DAT2_DAT2") (pintype "bidirectional"))
      (node (ref "R25") (pin "1") (pinfunction "1_1") (pintype "bidirectional"))
      (node (ref "U15") (pin "L1") (pinfunction "L1_L1") (pintype "bidirectional"))
    )
    (net (code "131") (name "SD_DAT3") (class "Default")
      (node (ref "J7") (pin "DAT3") (pinfunction "DAT3_DAT3") (pintype "bidirectional"))
      (node (ref "R26") (pin "1") (pinfunction "1_1") (pintype "bidirectional"))
      (node (ref "U15") (pin "L2") (pinfunction "L2_L2") (pintype "bidirectional"))
    )
    (net (code "132") (name "STM_BOOT") (class "Default")
      (node (ref "H1") (pin "8") (pinfunction "8_8") (pintype "bidirectional"))
      (node (ref "R31") (pin "2") (pinfunction "2_2") (pintype "bidirectional"))
      (node (ref "U19") (pin "D6") (pinfunction "BOOT0_D6_D6") (pintype "bidirectional"))
    )
    (net (code "133") (name "STM_CLK16MHZ") (class "Default")
      (node (ref "TP3") (pin "X") (pinfunction "X_X") (pintype "bidirectional"))
      (node (ref "U19") (pin "G1") (pinfunction "PH0_G1_G1") (pintype "bidirectional"))
      (node (ref "X3") (pin "2") (pinfunction "OUT_2") (pintype "bidirectional"))
    )
    (net (code "134") (name "STM_LED0") (class "Default")
      (node (ref "LED8") (pin "A") (pinfunction "A_A") (pintype "bidirectional"))
      (node (ref "U19") (pin "R7") (pinfunction "PF14_R7_R7") (pintype "bidirectional"))
    )
    (net (code "135") (name "STM_LED1") (class "Default")
      (node (ref "LED7") (pin "A") (pinfunction "A_A") (pintype "bidirectional"))
      (node (ref "U19") (pin "R8") (pinfunction "PE7_R8_R8") (pintype "bidirectional"))
    )
    (net (code "136") (name "STM_LED2") (class "Default")
      (node (ref "LED6") (pin "A") (pinfunction "A_A") (pintype "bidirectional"))
      (node (ref "U19") (pin "R9") (pinfunction "PE10_R9_R9") (pintype "bidirectional"))
    )
    (net (code "137") (name "STM_LED3") (class "Default")
      (node (ref "LED5") (pin "A") (pinfunction "A_A") (pintype "bidirectional"))
      (node (ref "U19") (pin "R10") (pinfunction "PE12_R10_R10") (pintype "bidirectional"))
    )
    (net (code "138") (name "STM_RST_") (class "Default")
      (node (ref "C68") (pin "1") (pinfunction "1_1") (pintype "bidirectional"))
      (node (ref "H1") (pin "7") (pinfunction "7_7") (pintype "bidirectional"))
      (node (ref "U19") (pin "J1") (pinfunction "NRST_J1_J1") (pintype "bidirectional"))
    )
    (net (code "139") (name "STM_SWCLK") (class "Default")
      (node (ref "H1") (pin "2") (pinfunction "2_2") (pintype "bidirectional"))
      (node (ref "U19") (pin "A14") (pinfunction "PA14_A14_A14") (pintype "bidirectional"))
    )
    (net (code "140") (name "STM_SWDIO") (class "Default")
      (node (ref "H1") (pin "1") (pinfunction "1_1") (pintype "bidirectional"))
      (node (ref "U19") (pin "A15") (pinfunction "PA13_A15_A15") (pintype "bidirectional"))
    )
    (net (code "141") (name "USB_D+") (class "Default")
      (node (ref "J8") (pin "D+") (pinfunction "D+_D+") (pintype "bidirectional"))
      (node (ref "U19") (pin "R15") (pinfunction "PB15_R15_R15") (pintype "bidirectional"))
      (node (ref "U20") (pin "3") (pinfunction "IO2_3") (pintype "bidirectional"))
    )
    (net (code "142") (name "USB_D-") (class "Default")
      (node (ref "J8") (pin "D-") (pinfunction "D-_D-") (pintype "bidirectional"))
      (node (ref "U19") (pin "R14") (pinfunction "PB14_R14_R14") (pintype "bidirectional"))
      (node (ref "U20") (pin "1") (pinfunction "IO1_1") (pintype "bidirectional"))
    )
    (net (code "143") (name "VCCPLL0") (class "Default")
      (node (ref "C45") (pin "1") (pinfunction "1_1") (pintype "bidirectional"))
      (node (ref "C46") (pin "1") (pinfunction "1_1") (pintype "bidirectional"))
      (node (ref "R17") (pin "1") (pinfunction "1_1") (pintype "bidirectional"))
      (node (ref "U15") (pin "J6") (pinfunction "VCCPLL0_J6_J6") (pintype "bidirectional"))
    )
    (net (code "144") (name "VCCPLL1") (class "Default")
      (node (ref "C42") (pin "1") (pinfunction "1_1") (pintype "bidirectional"))
      (node (ref "C43") (pin "1") (pinfunction "1_1") (pintype "bidirectional"))
      (node (ref "R16") (pin "1") (pinfunction "1_1") (pintype "bidirectional"))
      (node (ref "U15") (pin "C6") (pinfunction "VCCPLL1_C6_C6") (pintype "bidirectional"))
    )
    (net (code "145") (name "VDD_1V2") (class "Default")
      (node (ref "C30") (pin "1") (pinfunction "1_1") (pintype "bidirectional"))
      (node (ref "C31") (pin "1") (pinfunction "1_1") (pintype "bidirectional"))
      (node (ref "C32") (pin "1") (pinfunction "1_1") (pintype "bidirectional"))
      (node (ref "C33") (pin "1") (pinfunction "1_1") (pintype "bidirectional"))
      (node (ref "R16") (pin "2") (pinfunction "2_2") (pintype "bidirectional"))
      (node (ref "R17") (pin "2") (pinfunction "2_2") (pintype "bidirectional"))
      (node (ref "R5") (pin "1") (pinfunction "1_1") (pintype "bidirectional"))
      (node (ref "U15") (pin "D4") (pinfunction "VCC_D4_D4") (pintype "bidirectional"))
      (node (ref "U15") (pin "D8") (pinfunction "VCC_D8_D8") (pintype "bidirectional"))
      (node (ref "U15") (pin "H4") (pinfunction "VCC_H4_H4") (pintype "bidirectional"))
      (node (ref "U15") (pin "H8") (pinfunction "VCC_H8_H8") (pintype "bidirectional"))
    )
    (net (code "146") (name "VDD_1V9") (class "Default")
      (node (ref "C15") (pin "1") (pinfunction "1_1") (pintype "bidirectional"))
      (node (ref "C18") (pin "1") (pinfunction "1_1") (pintype "bidirectional"))
      (node (ref "C19") (pin "1") (pinfunction "1_1") (pintype "bidirectional"))
      (node (ref "C28") (pin "1") (pinfunction "1_1") (pintype "bidirectional"))
      (node (ref "C34") (pin "1") (pinfunction "1_1") (pintype "bidirectional"))
      (node (ref "C35") (pin "1") (pinfunction "1_1") (pintype "bidirectional"))
      (node (ref "C36") (pin "1") (pinfunction "1_1") (pintype "bidirectional"))
      (node (ref "C37") (pin "1") (pinfunction "1_1") (pintype "bidirectional"))
      (node (ref "C38") (pin "1") (pinfunction "1_1") (pintype "bidirectional"))
      (node (ref "C39") (pin "1") (pinfunction "1_1") (pintype "bidirectional"))
      (node (ref "C44") (pin "1") (pinfunction "1_1") (pintype "bidirectional"))
      (node (ref "C61") (pin "1") (pinfunction "1_1") (pintype "bidirectional"))
      (node (ref "C62") (pin "1") (pinfunction "1_1") (pintype "bidirectional"))
      (node (ref "C63") (pin "1") (pinfunction "1_1") (pintype "bidirectional"))
      (node (ref "C64") (pin "1") (pinfunction "1_1") (pintype "bidirectional"))
      (node (ref "R18") (pin "1") (pinfunction "1_1") (pintype "bidirectional"))
      (node (ref "R19") (pin "1") (pinfunction "1_1") (pintype "bidirectional"))
      (node (ref "R6") (pin "1") (pinfunction "1_1") (pintype "bidirectional"))
      (node (ref "U1") (pin "A1") (pinfunction "VIN_A1") (pintype "bidirectional"))
      (node (ref "U1") (pin "B1") (pinfunction "EN_B1") (pintype "bidirectional"))
      (node (ref "U10") (pin "1") (pinfunction "VIN_1") (pintype "bidirectional"))
      (node (ref "U13") (pin "13") (pinfunction "VCCB_13") (pintype "bidirectional"))
      (node (ref "U15") (pin "D6") (pinfunction "VCCIO_0_D6_D6") (pintype "bidirectional"))
      (node (ref "U15") (pin "E4") (pinfunction "VCCIO_3_E4_E4") (pintype "bidirectional"))
      (node (ref "U15") (pin "F8") (pinfunction "VCCIO_1_F8_F8") (pintype "bidirectional"))
      (node (ref "U15") (pin "G4") (pinfunction "VCCIO_3_G4_G4") (pintype "bidirectional"))
      (node (ref "U15") (pin "H6") (pinfunction "VCCIO_2_H6_H6") (pintype "bidirectional"))
      (node (ref "U15") (pin "L11") (pinfunction "VCC_SPI_L11_L11") (pintype "bidirectional"))
      (node (ref "U18") (pin "A7") (pinfunction "VDDQ_A7_A7") (pintype "bidirectional"))
      (node (ref "U18") (pin "A9") (pinfunction "VDD_A9_A9") (pintype "bidirectional"))
      (node (ref "U18") (pin "B3") (pinfunction "VDDQ_B3_B3") (pintype "bidirectional"))
      (node (ref "U18") (pin "C7") (pinfunction "VDDQ_C7_C7") (pintype "bidirectional"))
      (node (ref "U18") (pin "D3") (pinfunction "VDDQ_D3_D3") (pintype "bidirectional"))
      (node (ref "U18") (pin "E7") (pinfunction "VDD_E7_E7") (pintype "bidirectional"))
      (node (ref "U18") (pin "J9") (pinfunction "VDD_J9_J9") (pintype "bidirectional"))
      (node (ref "U6") (pin "1") (pinfunction "VIN_1") (pintype "bidirectional"))
      (node (ref "U9") (pin "1") (pinfunction "VIN_1") (pintype "bidirectional"))
      (node (ref "X2") (pin "3") (pinfunction "VDD_3") (pintype "bidirectional"))
    )
    (net (code "147") (name "VDD_1V9_IMG") (class "Default")
      (node (ref "C47") (pin "1") (pinfunction "1_1") (pintype "bidirectional"))
      (node (ref "C52") (pin "1") (pinfunction "1_1") (pintype "bidirectional"))
      (node (ref "C53") (pin "1") (pinfunction "1_1") (pintype "bidirectional"))
      (node (ref "C54") (pin "1") (pinfunction "1_1") (pintype "bidirectional"))
      (node (ref "C55") (pin "1") (pinfunction "1_1") (pintype "bidirectional"))
      (node (ref "C56") (pin "1") (pinfunction "1_1") (pintype "bidirectional"))
      (node (ref "C57") (pin "1") (pinfunction "1_1") (pintype "bidirectional"))
      (node (ref "C58") (pin "1") (pinfunction "1_1") (pintype "bidirectional"))
      (node (ref "R20") (pin "2") (pinfunction "2_2") (pintype "bidirectional"))
      (node (ref "R21") (pin "1") (pinfunction "1_1") (pintype "bidirectional"))
      (node (ref "U16") (pin "1") (pinfunction "EN_1") (pintype "bidirectional"))
      (node (ref "U16") (pin "5") (pinfunction "VDD_5") (pintype "bidirectional"))
      (node (ref "U17") (pin "A7") (pinfunction "VDD_IO_A7") (pintype "bidirectional"))
      (node (ref "U17") (pin "A8") (pinfunction "VDD_A8") (pintype "bidirectional"))
      (node (ref "U17") (pin "B1") (pinfunction "VDD_B1") (pintype "bidirectional"))
      (node (ref "U17") (pin "D2") (pinfunction "VDD_IO_D2") (pintype "bidirectional"))
      (node (ref "U17") (pin "D5") (pinfunction "VDD_IO_D5") (pintype "bidirectional"))
      (node (ref "U17") (pin "D6") (pinfunction "VDD_IO_D6") (pintype "bidirectional"))
      (node (ref "U17") (pin "E5") (pinfunction "VDD_IO_E5") (pintype "bidirectional"))
      (node (ref "U17") (pin "F6") (pinfunction "VDD_IO_F6") (pintype "bidirectional"))
      (node (ref "U17") (pin "G2") (pinfunction "VDD_G2") (pintype "bidirectional"))
      (node (ref "U17") (pin "G8") (pinfunction "VDD_G8") (pintype "bidirectional"))
      (node (ref "U17") (pin "H5") (pinfunction "VDD_IO_H5") (pintype "bidirectional"))
      (node (ref "U6") (pin "5") (pinfunction "QOD_5") (pintype "bidirectional"))
      (node (ref "U6") (pin "6") (pinfunction "VOUT_6") (pintype "bidirectional"))
    )
    (net (code "148") (name "VDD_1V9_IMG_EN") (class "Default")
      (node (ref "U12") (pin "2") (pinfunction "PA.0/P1.0/UCB0STE/A0/VEREF+_2") (pintype "bidirectional"))
      (node (ref "U6") (pin "3") (pinfunction "EN_3") (pintype "bidirectional"))
    )
    (net (code "149") (name "VDD_1V9_SD") (class "Default")
      (node (ref "R22") (pin "2") (pinfunction "2_2") (pintype "bidirectional"))
      (node (ref "R23") (pin "2") (pinfunction "2_2") (pintype "bidirectional"))
      (node (ref "R24") (pin "2") (pinfunction "2_2") (pintype "bidirectional"))
      (node (ref "R25") (pin "2") (pinfunction "2_2") (pintype "bidirectional"))
      (node (ref "R26") (pin "2") (pinfunction "2_2") (pintype "bidirectional"))
      (node (ref "U9") (pin "5") (pinfunction "QOD_5") (pintype "bidirectional"))
      (node (ref "U9") (pin "6") (pinfunction "VOUT_6") (pintype "bidirectional"))
    )
    (net (code "150") (name "VDD_1V9_STM") (class "Default")
      (node (ref "C67") (pin "1") (pinfunction "1_1") (pintype "bidirectional"))
      (node (ref "C70") (pin "1") (pinfunction "1_1") (pintype "bidirectional"))
      (node (ref "C71") (pin "1") (pinfunction "1_1") (pintype "bidirectional"))
      (node (ref "C72") (pin "1") (pinfunction "1_1") (pintype "bidirectional"))
      (node (ref "C73") (pin "1") (pinfunction "1_1") (pintype "bidirectional"))
      (node (ref "C74") (pin "1") (pinfunction "1_1") (pintype "bidirectional"))
      (node (ref "C75") (pin "1") (pinfunction "1_1") (pintype "bidirectional"))
      (node (ref "C76") (pin "1") (pinfunction "1_1") (pintype "bidirectional"))
      (node (ref "C77") (pin "1") (pinfunction "1_1") (pintype "bidirectional"))
      (node (ref "C80") (pin "1") (pinfunction "1_1") (pintype "bidirectional"))
      (node (ref "C81") (pin "1") (pinfunction "1_1") (pintype "bidirectional"))
      (node (ref "C82") (pin "1") (pinfunction "1_1") (pintype "bidirectional"))
      (node (ref "C83") (pin "1") (pinfunction "1_1") (pintype "bidirectional"))
      (node (ref "C84") (pin "1") (pinfunction "1_1") (pintype "bidirectional"))
      (node (ref "C85") (pin "1") (pinfunction "1_1") (pintype "bidirectional"))
      (node (ref "C88") (pin "1") (pinfunction "1_1") (pintype "bidirectional"))
      (node (ref "U10") (pin "5") (pinfunction "QOD_5") (pintype "bidirectional"))
      (node (ref "U10") (pin "6") (pinfunction "VOUT_6") (pintype "bidirectional"))
      (node (ref "U11") (pin "3") (pinfunction "EN_3") (pintype "bidirectional"))
      (node (ref "U19") (pin "C1") (pinfunction "VBAT_C1_C1") (pintype "bidirectional"))
      (node (ref "U19") (pin "C5") (pinfunction "VDD_C5_C5") (pintype "bidirectional"))
      (node (ref "U19") (pin "C6") (pinfunction "PDR_ON_C6_C6") (pintype "bidirectional"))
      (node (ref "U19") (pin "C7") (pinfunction "VDD_C7_C7") (pintype "bidirectional"))
      (node (ref "U19") (pin "C8") (pinfunction "VDDSDMMC_C8_C8") (pintype "bidirectional"))
      (node (ref "U19") (pin "C9") (pinfunction "VDD_C9_C9") (pintype "bidirectional"))
      (node (ref "U19") (pin "F3") (pinfunction "VDD_F3_F3") (pintype "bidirectional"))
      (node (ref "U19") (pin "G13") (pinfunction "VDD_G13_G13") (pintype "bidirectional"))
      (node (ref "U19") (pin "G3") (pinfunction "VDD_G3_G3") (pintype "bidirectional"))
      (node (ref "U19") (pin "J12") (pinfunction "VDD_J12_J12") (pintype "bidirectional"))
      (node (ref "U19") (pin "J13") (pinfunction "VDD_J13_J13") (pintype "bidirectional"))
      (node (ref "U19") (pin "K4") (pinfunction "VDD_K4_K4") (pintype "bidirectional"))
      (node (ref "U19") (pin "N10") (pinfunction "VDD_N10_N10") (pintype "bidirectional"))
      (node (ref "U19") (pin "N8") (pinfunction "VDD_N8_N8") (pintype "bidirectional"))
      (node (ref "U19") (pin "N9") (pinfunction "VDD_N9_N9") (pintype "bidirectional"))
      (node (ref "U19") (pin "P1") (pinfunction "VREF+_P1_P1") (pintype "bidirectional"))
      (node (ref "U19") (pin "R1") (pinfunction "VDDA_R1_R1") (pintype "bidirectional"))
      (node (ref "X3") (pin "3") (pinfunction "VDD_3") (pintype "bidirectional"))
    )
    (net (code "151") (name "VDD_2V8") (class "Default")
      (node (ref "C16") (pin "1") (pinfunction "1_1") (pintype "bidirectional"))
      (node (ref "C17") (pin "1") (pinfunction "1_1") (pintype "bidirectional"))
      (node (ref "C40") (pin "1") (pinfunction "1_1") (pintype "bidirectional"))
      (node (ref "C41") (pin "1") (pinfunction "1_1") (pintype "bidirectional"))
      (node (ref "R8") (pin "1") (pinfunction "1_1") (pintype "bidirectional"))
      (node (ref "U15") (pin "C10") (pinfunction "VPP_2V5_C10_C10") (pintype "bidirectional"))
      (node (ref "U7") (pin "1") (pinfunction "VIN_1") (pintype "bidirectional"))
      (node (ref "U8") (pin "1") (pinfunction "VIN_1") (pintype "bidirectional"))
    )
    (net (code "152") (name "VDD_2V8_IMG") (class "Default")
      (node (ref "C48") (pin "1") (pinfunction "1_1") (pintype "bidirectional"))
      (node (ref "C49") (pin "1") (pinfunction "1_1") (pintype "bidirectional"))
      (node (ref "C50") (pin "1") (pinfunction "1_1") (pintype "bidirectional"))
      (node (ref "C51") (pin "1") (pinfunction "1_1") (pintype "bidirectional"))
      (node (ref "C59") (pin "1") (pinfunction "1_1") (pintype "bidirectional"))
      (node (ref "C60") (pin "1") (pinfunction "1_1") (pintype "bidirectional"))
      (node (ref "U17") (pin "A1") (pinfunction "VAA_A1") (pintype "bidirectional"))
      (node (ref "U17") (pin "A5") (pinfunction "VAA_PIX_A5") (pintype "bidirectional"))
      (node (ref "U17") (pin "A6") (pinfunction "VAA_A6") (pintype "bidirectional"))
      (node (ref "U17") (pin "F8") (pinfunction "VDD_PLL_F8") (pintype "bidirectional"))
      (node (ref "U17") (pin "H6") (pinfunction "VDD_MIPI_H6") (pintype "bidirectional"))
      (node (ref "U17") (pin "H8") (pinfunction "VDD_MIPI_H8") (pintype "bidirectional"))
      (node (ref "U7") (pin "5") (pinfunction "QOD_5") (pintype "bidirectional"))
      (node (ref "U7") (pin "6") (pinfunction "VOUT_6") (pintype "bidirectional"))
    )
    (net (code "153") (name "VDD_2V8_IMG_EN") (class "Default")
      (node (ref "U12") (pin "20") (pinfunction "PA.2/P1.2/UCB0SIMO/UCB0SDA/SMCLK/A2/VEREF-_20") (pintype "bidirectional"))
      (node (ref "U7") (pin "3") (pinfunction "EN_3") (pintype "bidirectional"))
    )
    (net (code "154") (name "VDD_2V8_SD") (class "Default")
      (node (ref "C65") (pin "1") (pinfunction "1_1") (pintype "bidirectional"))
      (node (ref "C66") (pin "1") (pinfunction "1_1") (pintype "bidirectional"))
      (node (ref "J7") (pin "VDD") (pinfunction "VDD_VDD") (pintype "bidirectional"))
      (node (ref "U8") (pin "5") (pinfunction "QOD_5") (pintype "bidirectional"))
      (node (ref "U8") (pin "6") (pinfunction "VOUT_6") (pintype "bidirectional"))
    )
    (net (code "155") (name "VDD_3V3_STM") (class "Default")
      (node (ref "C21") (pin "1") (pinfunction "1_1") (pintype "bidirectional"))
      (node (ref "C78") (pin "1") (pinfunction "1_1") (pintype "bidirectional"))
      (node (ref "C79") (pin "1") (pinfunction "1_1") (pintype "bidirectional"))
      (node (ref "U11") (pin "5") (pinfunction "VOUT_5") (pintype "bidirectional"))
      (node (ref "U19") (pin "H13") (pinfunction "VDDUSB_H13_H13") (pintype "bidirectional"))
    )
    (net (code "156") (name "VDD_A") (class "Default")
      (node (ref "C24") (pin "1") (pinfunction "1_1") (pintype "bidirectional"))
      (node (ref "C25") (pin "1") (pinfunction "1_1") (pintype "bidirectional"))
      (node (ref "C27") (pin "1") (pinfunction "1_1") (pintype "bidirectional"))
      (node (ref "C29") (pin "1") (pinfunction "1_1") (pintype "bidirectional"))
      (node (ref "J1") (pin "2") (pinfunction "2_2") (pintype "bidirectional"))
      (node (ref "R11") (pin "2") (pinfunction "2_2") (pintype "bidirectional"))
      (node (ref "U12") (pin "5") (pinfunction "VDD_5") (pintype "bidirectional"))
      (node (ref "U13") (pin "14") (pinfunction "VCCA_14") (pintype "bidirectional"))
      (node (ref "U13") (pin "16") (pinfunction "DIR2_16") (pintype "bidirectional"))
      (node (ref "U14") (pin "1") (pinfunction "VDD_1") (pintype "bidirectional"))
    )
    (net (code "157") (name "VDD_B") (class "Default")
      (node (ref "C11") (pin "1") (pinfunction "1_1") (pintype "bidirectional"))
      (node (ref "C12") (pin "1") (pinfunction "1_1") (pintype "bidirectional"))
      (node (ref "C5") (pin "1") (pinfunction "1_1") (pintype "bidirectional"))
      (node (ref "C6") (pin "1") (pinfunction "1_1") (pintype "bidirectional"))
      (node (ref "C8") (pin "1") (pinfunction "1_1") (pintype "bidirectional"))
      (node (ref "C9") (pin "1") (pinfunction "1_1") (pintype "bidirectional"))
      (node (ref "J3") (pin "2") (pinfunction "2_2") (pintype "bidirectional"))
      (node (ref "U3") (pin "B1") (pinfunction "VIN_B1") (pintype "bidirectional"))
      (node (ref "U3") (pin "C2") (pinfunction "EN_C2") (pintype "bidirectional"))
      (node (ref "U4") (pin "B1") (pinfunction "VIN_B1") (pintype "bidirectional"))
      (node (ref "U4") (pin "C2") (pinfunction "EN_C2") (pintype "bidirectional"))
      (node (ref "U5") (pin "A1") (pinfunction "EN_A1") (pintype "bidirectional"))
      (node (ref "U5") (pin "A2") (pinfunction "VIN_A2") (pintype "bidirectional"))
      (node (ref "U5") (pin "A3") (pinfunction "VIN_A3") (pintype "bidirectional"))
    )
    (net (code "158") (name "VDD_BAT_IN") (class "Default")
      (node (ref "J2") (pin "1") (pinfunction "1_1") (pintype "bidirectional"))
    )
    (net (code "159") (name "VDD_B_EN_") (class "Default")
      (node (ref "R4") (pin "2") (pinfunction "2_2") (pintype "bidirectional"))
      (node (ref "U12") (pin "11") (pinfunction "PA.C/P2.4/TA1CLK/UCB0CLK/A6_11") (pintype "bidirectional"))
    )
    (net (code "160") (name "VDD_SD_EN") (class "Default")
      (node (ref "U12") (pin "12") (pinfunction "PA.B/P2.3/TA1.2/UCB0STE/A5_12") (pintype "bidirectional"))
      (node (ref "U8") (pin "3") (pinfunction "EN_3") (pintype "bidirectional"))
      (node (ref "U9") (pin "3") (pinfunction "EN_3") (pintype "bidirectional"))
    )
    (net (code "161") (name "VDD_SRC_USB") (class "Default")
      (node (ref "Q1") (pin "3") (pinfunction "G_3") (pintype "bidirectional"))
      (node (ref "Q2") (pin "3") (pinfunction "G_3") (pintype "bidirectional"))
      (node (ref "R1") (pin "1") (pinfunction "1_1") (pintype "bidirectional"))
      (node (ref "R2") (pin "2") (pinfunction "2_2") (pintype "bidirectional"))
    )
    (net (code "162") (name "VDD_USB") (class "Default")
      (node (ref "C20") (pin "1") (pinfunction "1_1") (pintype "bidirectional"))
      (node (ref "D1") (pin "1") (pinfunction "A_1") (pintype "bidirectional"))
      (node (ref "R1") (pin "2") (pinfunction "2_2") (pintype "bidirectional"))
      (node (ref "U10") (pin "3") (pinfunction "EN_3") (pintype "bidirectional"))
      (node (ref "U11") (pin "1") (pinfunction "VIN_1") (pintype "bidirectional"))
      (node (ref "U2") (pin "6") (pinfunction "VOUT_6") (pintype "bidirectional"))
    )
    (net (code "163") (name "VDD_USB_IN") (class "Default")
      (node (ref "FB1") (pin "2") (pinfunction "P$2_2") (pintype "bidirectional"))
      (node (ref "H1") (pin "9") (pinfunction "9_9") (pintype "bidirectional"))
      (node (ref "J4") (pin "1") (pinfunction "1_1") (pintype "bidirectional"))
    )
    (net (code "164") (name "unconnected-(H1-Pad3)") (class "Default")
      (node (ref "H1") (pin "3") (pinfunction "3_3") (pintype "bidirectional"))
    )
    (net (code "165") (name "unconnected-(H1-Pad4)") (class "Default")
      (node (ref "H1") (pin "4") (pinfunction "4_4") (pintype "bidirectional"))
    )
    (net (code "166") (name "unconnected-(H1-Pad5)") (class "Default")
      (node (ref "H1") (pin "5") (pinfunction "5_5") (pintype "bidirectional"))
    )
    (net (code "167") (name "unconnected-(H1-Pad6)") (class "Default")
      (node (ref "H1") (pin "6") (pinfunction "6_6") (pintype "bidirectional"))
    )
    (net (code "168") (name "unconnected-(J7-PadDET)") (class "Default")
      (node (ref "J7") (pin "DET") (pinfunction "DET_DET") (pintype "bidirectional"))
    )
    (net (code "169") (name "unconnected-(J8-PadID)") (class "Default")
      (node (ref "J8") (pin "ID") (pinfunction "ID_ID") (pintype "bidirectional"))
    )
    (net (code "170") (name "unconnected-(U2-QOD-Pad5)") (class "Default")
      (node (ref "U2") (pin "5") (pinfunction "QOD_5") (pintype "bidirectional"))
    )
    (net (code "171") (name "unconnected-(U5-PG-PadE1)") (class "Default")
      (node (ref "U5") (pin "E1") (pinfunction "PG_E1") (pintype "bidirectional"))
    )
    (net (code "172") (name "unconnected-(U12C-PA.E{slash}P2.6{slash}UCB0SOMI{slash}UCB0SCL-Pad9)") (class "Default")
      (node (ref "U12") (pin "9") (pinfunction "PA.E/P2.6/UCB0SOMI/UCB0SCL_9") (pintype "bidirectional"))
    )
    (net (code "173") (name "unconnected-(U13-A4-Pad4)") (class "Default")
      (node (ref "U13") (pin "4") (pinfunction "A4_4") (pintype "bidirectional"))
    )
    (net (code "174") (name "unconnected-(U13-B4-Pad9)") (class "Default")
      (node (ref "U13") (pin "9") (pinfunction "B4_9") (pintype "bidirectional"))
    )
    (net (code "175") (name "unconnected-(U13-DIR4-Pad6)") (class "Default")
      (node (ref "U13") (pin "6") (pinfunction "DIR4_6") (pintype "bidirectional"))
    )
    (net (code "176") (name "unconnected-(U15-PadC8)") (class "Default")
      (node (ref "U15") (pin "C8") (pinfunction "C8_C8") (pintype "bidirectional"))
    )
    (net (code "177") (name "unconnected-(U15-PadD9)") (class "Default")
      (node (ref "U15") (pin "D9") (pinfunction "D9_D9") (pintype "bidirectional"))
    )
    (net (code "178") (name "unconnected-(U15-PadE3)") (class "Default")
      (node (ref "U15") (pin "E3") (pinfunction "E3_E3") (pintype "bidirectional"))
    )
    (net (code "179") (name "unconnected-(U15-PadF3)") (class "Default")
      (node (ref "U15") (pin "F3") (pinfunction "F3_F3") (pintype "bidirectional"))
    )
    (net (code "180") (name "unconnected-(U15-PadF4)") (class "Default")
      (node (ref "U15") (pin "F4") (pinfunction "F4_F4") (pintype "bidirectional"))
    )
    (net (code "181") (name "unconnected-(U15-PadG3)") (class "Default")
      (node (ref "U15") (pin "G3") (pinfunction "G3_G3") (pintype "bidirectional"))
    )
    (net (code "182") (name "unconnected-(U15-PadH3)") (class "Default")
      (node (ref "U15") (pin "H3") (pinfunction "H3_H3") (pintype "bidirectional"))
    )
    (net (code "183") (name "unconnected-(U15-PadH9)") (class "Default")
      (node (ref "U15") (pin "H9") (pinfunction "H9_H9") (pintype "bidirectional"))
    )
    (net (code "184") (name "unconnected-(U15-PadJ3)") (class "Default")
      (node (ref "U15") (pin "J3") (pinfunction "J3_J3") (pintype "bidirectional"))
    )
    (net (code "185") (name "unconnected-(U15-PadJ4)") (class "Default")
      (node (ref "U15") (pin "J4") (pinfunction "J4_J4") (pintype "bidirectional"))
    )
    (net (code "186") (name "unconnected-(U15-PadJ5)") (class "Default")
      (node (ref "U15") (pin "J5") (pinfunction "J5_J5") (pintype "bidirectional"))
    )
    (net (code "187") (name "unconnected-(U15-PadJ8)") (class "Default")
      (node (ref "U15") (pin "J8") (pinfunction "J8_J8") (pintype "bidirectional"))
    )
    (net (code "188") (name "unconnected-(U15-PadL5)") (class "Default")
      (node (ref "U15") (pin "L5") (pinfunction "L5_L5") (pintype "bidirectional"))
    )
    (net (code "189") (name "unconnected-(U15E-VPP_FAST_B10-PadB10)") (class "Default")
      (node (ref "U15") (pin "B10") (pinfunction "VPP_FAST_B10_B10") (pintype "bidirectional"))
    )
    (net (code "190") (name "unconnected-(U17A-VAAHV_NPIX-PadA2)") (class "Default")
      (node (ref "U17") (pin "A2") (pinfunction "VAAHV_NPIX_A2") (pintype "bidirectional"))
    )
    (net (code "191") (name "unconnected-(U17B-CLK_N-PadE7)") (class "Default")
      (node (ref "U17") (pin "E7") (pinfunction "CLK_N_E7") (pintype "bidirectional"))
    )
    (net (code "192") (name "unconnected-(U17B-CLK_P-PadF7)") (class "Default")
      (node (ref "U17") (pin "F7") (pinfunction "CLK_P_F7") (pintype "bidirectional"))
    )
    (net (code "193") (name "unconnected-(U17B-DATA2_N-PadG7)") (class "Default")
      (node (ref "U17") (pin "G7") (pinfunction "DATA2_N_G7") (pintype "bidirectional"))
    )
    (net (code "194") (name "unconnected-(U17B-DATA2_P-PadH7)") (class "Default")
      (node (ref "U17") (pin "H7") (pinfunction "DATA2_P_H7") (pintype "bidirectional"))
    )
    (net (code "195") (name "unconnected-(U17B-DATA_N-PadD8)") (class "Default")
      (node (ref "U17") (pin "D8") (pinfunction "DATA_N_D8") (pintype "bidirectional"))
    )
    (net (code "196") (name "unconnected-(U17B-DATA_P-PadE8)") (class "Default")
      (node (ref "U17") (pin "E8") (pinfunction "DATA_P_E8") (pintype "bidirectional"))
    )
    (net (code "197") (name "unconnected-(U17B-FLASH-PadC2)") (class "Default")
      (node (ref "U17") (pin "C2") (pinfunction "FLASH_C2") (pintype "bidirectional"))
    )
    (net (code "198") (name "unconnected-(U17B-SHUTTER-PadB8)") (class "Default")
      (node (ref "U17") (pin "B8") (pinfunction "SHUTTER_B8") (pintype "bidirectional"))
    )
    (net (code "199") (name "unconnected-(U17B-TRIGGER-PadC7)") (class "Default")
      (node (ref "U17") (pin "C7") (pinfunction "TRIGGER_C7") (pintype "bidirectional"))
    )
    (net (code "200") (name "unconnected-(U19A-PA0_N3-PadN3)") (class "Default")
      (node (ref "U19") (pin "N3") (pinfunction "PA0_N3_N3") (pintype "bidirectional"))
    )
    (net (code "201") (name "unconnected-(U19A-PA1_N2-PadN2)") (class "Default")
      (node (ref "U19") (pin "N2") (pinfunction "PA1_N2_N2") (pintype "bidirectional"))
    )
    (net (code "202") (name "unconnected-(U19A-PA2_P2-PadP2)") (class "Default")
      (node (ref "U19") (pin "P2") (pinfunction "PA2_P2_P2") (pintype "bidirectional"))
    )
    (net (code "203") (name "unconnected-(U19A-PA3_R2-PadR2)") (class "Default")
      (node (ref "U19") (pin "R2") (pinfunction "PA3_R2_R2") (pintype "bidirectional"))
    )
    (net (code "204") (name "unconnected-(U19A-PA4_N4-PadN4)") (class "Default")
      (node (ref "U19") (pin "N4") (pinfunction "PA4_N4_N4") (pintype "bidirectional"))
    )
    (net (code "205") (name "unconnected-(U19A-PA5_P4-PadP4)") (class "Default")
      (node (ref "U19") (pin "P4") (pinfunction "PA5_P4_P4") (pintype "bidirectional"))
    )
    (net (code "206") (name "unconnected-(U19A-PA6_P3-PadP3)") (class "Default")
      (node (ref "U19") (pin "P3") (pinfunction "PA6_P3_P3") (pintype "bidirectional"))
    )
    (net (code "207") (name "unconnected-(U19A-PA7_R3-PadR3)") (class "Default")
      (node (ref "U19") (pin "R3") (pinfunction "PA7_R3_R3") (pintype "bidirectional"))
    )
    (net (code "208") (name "unconnected-(U19A-PA8_F15-PadF15)") (class "Default")
      (node (ref "U19") (pin "F15") (pinfunction "PA8_F15_F15") (pintype "bidirectional"))
    )
    (net (code "209") (name "unconnected-(U19A-PA9_E15-PadE15)") (class "Default")
      (node (ref "U19") (pin "E15") (pinfunction "PA9_E15_E15") (pintype "bidirectional"))
    )
    (net (code "210") (name "unconnected-(U19A-PA10_D15-PadD15)") (class "Default")
      (node (ref "U19") (pin "D15") (pinfunction "PA10_D15_D15") (pintype "bidirectional"))
    )
    (net (code "211") (name "unconnected-(U19A-PA11_C15-PadC15)") (class "Default")
      (node (ref "U19") (pin "C15") (pinfunction "PA11_C15_C15") (pintype "bidirectional"))
    )
    (net (code "212") (name "unconnected-(U19A-PA12_B15-PadB15)") (class "Default")
      (node (ref "U19") (pin "B15") (pinfunction "PA12_B15_B15") (pintype "bidirectional"))
    )
    (net (code "213") (name "unconnected-(U19A-PA15_A13-PadA13)") (class "Default")
      (node (ref "U19") (pin "A13") (pinfunction "PA15_A13_A13") (pintype "bidirectional"))
    )
    (net (code "214") (name "unconnected-(U19B-PB3_A10-PadA10)") (class "Default")
      (node (ref "U19") (pin "A10") (pinfunction "PB3_A10_A10") (pintype "bidirectional"))
    )
    (net (code "215") (name "unconnected-(U19B-PB4_A9-PadA9)") (class "Default")
      (node (ref "U19") (pin "A9") (pinfunction "PB4_A9_A9") (pintype "bidirectional"))
    )
    (net (code "216") (name "unconnected-(U19B-PB5_A6-PadA6)") (class "Default")
      (node (ref "U19") (pin "A6") (pinfunction "PB5_A6_A6") (pintype "bidirectional"))
    )
    (net (code "217") (name "unconnected-(U19B-PB7_B5-PadB5)") (class "Default")
      (node (ref "U19") (pin "B5") (pinfunction "PB7_B5_B5") (pintype "bidirectional"))
    )
    (net (code "218") (name "unconnected-(U19B-PB8_A5-PadA5)") (class "Default")
      (node (ref "U19") (pin "A5") (pinfunction "PB8_A5_A5") (pintype "bidirectional"))
    )
    (net (code "219") (name "unconnected-(U19B-PB9_B4-PadB4)") (class "Default")
      (node (ref "U19") (pin "B4") (pinfunction "PB9_B4_B4") (pintype "bidirectional"))
    )
    (net (code "220") (name "unconnected-(U19B-PB10_R12-PadR12)") (class "Default")
      (node (ref "U19") (pin "R12") (pinfunction "PB10_R12_R12") (pintype "bidirectional"))
    )
    (net (code "221") (name "unconnected-(U19B-PB11_R13-PadR13)") (class "Default")
      (node (ref "U19") (pin "R13") (pinfunction "PB11_R13_R13") (pintype "bidirectional"))
    )
    (net (code "222") (name "unconnected-(U19B-PB12_P12-PadP12)") (class "Default")
      (node (ref "U19") (pin "P12") (pinfunction "PB12_P12_P12") (pintype "bidirectional"))
    )
    (net (code "223") (name "unconnected-(U19B-PB13_P13-PadP13)") (class "Default")
      (node (ref "U19") (pin "P13") (pinfunction "PB13_P13_P13") (pintype "bidirectional"))
    )
    (net (code "224") (name "unconnected-(U19C-PC0_M2-PadM2)") (class "Default")
      (node (ref "U19") (pin "M2") (pinfunction "PC0_M2_M2") (pintype "bidirectional"))
    )
    (net (code "225") (name "unconnected-(U19C-PC1_M3-PadM3)") (class "Default")
      (node (ref "U19") (pin "M3") (pinfunction "PC1_M3_M3") (pintype "bidirectional"))
    )
    (net (code "226") (name "unconnected-(U19C-PC2_M4-PadM4)") (class "Default")
      (node (ref "U19") (pin "M4") (pinfunction "PC2_M4_M4") (pintype "bidirectional"))
    )
    (net (code "227") (name "unconnected-(U19C-PC3_M5-PadM5)") (class "Default")
      (node (ref "U19") (pin "M5") (pinfunction "PC3_M5_M5") (pintype "bidirectional"))
    )
    (net (code "228") (name "unconnected-(U19C-PC4_N5-PadN5)") (class "Default")
      (node (ref "U19") (pin "N5") (pinfunction "PC4_N5_N5") (pintype "bidirectional"))
    )
    (net (code "229") (name "unconnected-(U19C-PC5_P5-PadP5)") (class "Default")
      (node (ref "U19") (pin "P5") (pinfunction "PC5_P5_P5") (pintype "bidirectional"))
    )
    (net (code "230") (name "unconnected-(U19C-PC6_H15-PadH15)") (class "Default")
      (node (ref "U19") (pin "H15") (pinfunction "PC6_H15_H15") (pintype "bidirectional"))
    )
    (net (code "231") (name "unconnected-(U19C-PC7_G15-PadG15)") (class "Default")
      (node (ref "U19") (pin "G15") (pinfunction "PC7_G15_G15") (pintype "bidirectional"))
    )
    (net (code "232") (name "unconnected-(U19C-PC8_G14-PadG14)") (class "Default")
      (node (ref "U19") (pin "G14") (pinfunction "PC8_G14_G14") (pintype "bidirectional"))
    )
    (net (code "233") (name "unconnected-(U19C-PC11_B13-PadB13)") (class "Default")
      (node (ref "U19") (pin "B13") (pinfunction "PC11_B13_B13") (pintype "bidirectional"))
    )
    (net (code "234") (name "unconnected-(U19C-PC12_A12-PadA12)") (class "Default")
      (node (ref "U19") (pin "A12") (pinfunction "PC12_A12_A12") (pintype "bidirectional"))
    )
    (net (code "235") (name "unconnected-(U19C-PC13_D1-PadD1)") (class "Default")
      (node (ref "U19") (pin "D1") (pinfunction "PC13_D1_D1") (pintype "bidirectional"))
    )
    (net (code "236") (name "unconnected-(U19C-PC14_E1-PadE1)") (class "Default")
      (node (ref "U19") (pin "E1") (pinfunction "PC14_E1_E1") (pintype "bidirectional"))
    )
    (net (code "237") (name "unconnected-(U19C-PC15_F1-PadF1)") (class "Default")
      (node (ref "U19") (pin "F1") (pinfunction "PC15_F1_F1") (pintype "bidirectional"))
    )
    (net (code "238") (name "unconnected-(U19D-PD0_B12-PadB12)") (class "Default")
      (node (ref "U19") (pin "B12") (pinfunction "PD0_B12_B12") (pintype "bidirectional"))
    )
    (net (code "239") (name "unconnected-(U19D-PD1_C12-PadC12)") (class "Default")
      (node (ref "U19") (pin "C12") (pinfunction "PD1_C12_C12") (pintype "bidirectional"))
    )
    (net (code "240") (name "unconnected-(U19D-PD2_D12-PadD12)") (class "Default")
      (node (ref "U19") (pin "D12") (pinfunction "PD2_D12_D12") (pintype "bidirectional"))
    )
    (net (code "241") (name "unconnected-(U19D-PD3_D11-PadD11)") (class "Default")
      (node (ref "U19") (pin "D11") (pinfunction "PD3_D11_D11") (pintype "bidirectional"))
    )
    (net (code "242") (name "unconnected-(U19D-PD4_D10-PadD10)") (class "Default")
      (node (ref "U19") (pin "D10") (pinfunction "PD4_D10_D10") (pintype "bidirectional"))
    )
    (net (code "243") (name "unconnected-(U19D-PD5_C11-PadC11)") (class "Default")
      (node (ref "U19") (pin "C11") (pinfunction "PD5_C11_C11") (pintype "bidirectional"))
    )
    (net (code "244") (name "unconnected-(U19D-PD6_B11-PadB11)") (class "Default")
      (node (ref "U19") (pin "B11") (pinfunction "PD6_B11_B11") (pintype "bidirectional"))
    )
    (net (code "245") (name "unconnected-(U19D-PD7_A11-PadA11)") (class "Default")
      (node (ref "U19") (pin "A11") (pinfunction "PD7_A11_A11") (pintype "bidirectional"))
    )
    (net (code "246") (name "unconnected-(U19D-PD8_P15-PadP15)") (class "Default")
      (node (ref "U19") (pin "P15") (pinfunction "PD8_P15_P15") (pintype "bidirectional"))
    )
    (net (code "247") (name "unconnected-(U19D-PD9_P14-PadP14)") (class "Default")
      (node (ref "U19") (pin "P14") (pinfunction "PD9_P14_P14") (pintype "bidirectional"))
    )
    (net (code "248") (name "unconnected-(U19D-PD10_N15-PadN15)") (class "Default")
      (node (ref "U19") (pin "N15") (pinfunction "PD10_N15_N15") (pintype "bidirectional"))
    )
    (net (code "249") (name "unconnected-(U19D-PD11_N14-PadN14)") (class "Default")
      (node (ref "U19") (pin "N14") (pinfunction "PD11_N14_N14") (pintype "bidirectional"))
    )
    (net (code "250") (name "unconnected-(U19D-PD12_N13-PadN13)") (class "Default")
      (node (ref "U19") (pin "N13") (pinfunction "PD12_N13_N13") (pintype "bidirectional"))
    )
    (net (code "251") (name "unconnected-(U19D-PD13_M15-PadM15)") (class "Default")
      (node (ref "U19") (pin "M15") (pinfunction "PD13_M15_M15") (pintype "bidirectional"))
    )
    (net (code "252") (name "unconnected-(U19D-PD14_M14-PadM14)") (class "Default")
      (node (ref "U19") (pin "M14") (pinfunction "PD14_M14_M14") (pintype "bidirectional"))
    )
    (net (code "253") (name "unconnected-(U19D-PD15_L14-PadL14)") (class "Default")
      (node (ref "U19") (pin "L14") (pinfunction "PD15_L14_L14") (pintype "bidirectional"))
    )
    (net (code "254") (name "unconnected-(U19E-PE0_A4-PadA4)") (class "Default")
      (node (ref "U19") (pin "A4") (pinfunction "PE0_A4_A4") (pintype "bidirectional"))
    )
    (net (code "255") (name "unconnected-(U19E-PE1_A3-PadA3)") (class "Default")
      (node (ref "U19") (pin "A3") (pinfunction "PE1_A3_A3") (pintype "bidirectional"))
    )
    (net (code "256") (name "unconnected-(U19E-PE2_A2-PadA2)") (class "Default")
      (node (ref "U19") (pin "A2") (pinfunction "PE2_A2_A2") (pintype "bidirectional"))
    )
    (net (code "257") (name "unconnected-(U19E-PE3_A1-PadA1)") (class "Default")
      (node (ref "U19") (pin "A1") (pinfunction "PE3_A1_A1") (pintype "bidirectional"))
    )
    (net (code "258") (name "unconnected-(U19E-PE4_B1-PadB1)") (class "Default")
      (node (ref "U19") (pin "B1") (pinfunction "PE4_B1_B1") (pintype "bidirectional"))
    )
    (net (code "259") (name "unconnected-(U19E-PE5_B2-PadB2)") (class "Default")
      (node (ref "U19") (pin "B2") (pinfunction "PE5_B2_B2") (pintype "bidirectional"))
    )
    (net (code "260") (name "unconnected-(U19E-PE6_B3-PadB3)") (class "Default")
      (node (ref "U19") (pin "B3") (pinfunction "PE6_B3_B3") (pintype "bidirectional"))
    )
    (net (code "261") (name "unconnected-(U19E-PE8_P8-PadP8)") (class "Default")
      (node (ref "U19") (pin "P8") (pinfunction "PE8_P8_P8") (pintype "bidirectional"))
    )
    (net (code "262") (name "unconnected-(U19E-PE9_P9-PadP9)") (class "Default")
      (node (ref "U19") (pin "P9") (pinfunction "PE9_P9_P9") (pintype "bidirectional"))
    )
    (net (code "263") (name "unconnected-(U19E-PE11_P10-PadP10)") (class "Default")
      (node (ref "U19") (pin "P10") (pinfunction "PE11_P10_P10") (pintype "bidirectional"))
    )
    (net (code "264") (name "unconnected-(U19E-PE13_N11-PadN11)") (class "Default")
      (node (ref "U19") (pin "N11") (pinfunction "PE13_N11_N11") (pintype "bidirectional"))
    )
    (net (code "265") (name "unconnected-(U19E-PE14_P11-PadP11)") (class "Default")
      (node (ref "U19") (pin "P11") (pinfunction "PE14_P11_P11") (pintype "bidirectional"))
    )
    (net (code "266") (name "unconnected-(U19E-PE15_R11-PadR11)") (class "Default")
      (node (ref "U19") (pin "R11") (pinfunction "PE15_R11_R11") (pintype "bidirectional"))
    )
    (net (code "267") (name "unconnected-(U19F-PF0_E2-PadE2)") (class "Default")
      (node (ref "U19") (pin "E2") (pinfunction "PF0_E2_E2") (pintype "bidirectional"))
    )
    (net (code "268") (name "unconnected-(U19F-PF1_H3-PadH3)") (class "Default")
      (node (ref "U19") (pin "H3") (pinfunction "PF1_H3_H3") (pintype "bidirectional"))
    )
    (net (code "269") (name "unconnected-(U19F-PF2_H2-PadH2)") (class "Default")
      (node (ref "U19") (pin "H2") (pinfunction "PF2_H2_H2") (pintype "bidirectional"))
    )
    (net (code "270") (name "unconnected-(U19F-PF3_J2-PadJ2)") (class "Default")
      (node (ref "U19") (pin "J2") (pinfunction "PF3_J2_J2") (pintype "bidirectional"))
    )
    (net (code "271") (name "unconnected-(U19F-PF4_J3-PadJ3)") (class "Default")
      (node (ref "U19") (pin "J3") (pinfunction "PF4_J3_J3") (pintype "bidirectional"))
    )
    (net (code "272") (name "unconnected-(U19F-PF5_K3-PadK3)") (class "Default")
      (node (ref "U19") (pin "K3") (pinfunction "PF5_K3_K3") (pintype "bidirectional"))
    )
    (net (code "273") (name "unconnected-(U19F-PF8_L3-PadL3)") (class "Default")
      (node (ref "U19") (pin "L3") (pinfunction "PF8_L3_L3") (pintype "bidirectional"))
    )
    (net (code "274") (name "unconnected-(U19F-PF9_L2-PadL2)") (class "Default")
      (node (ref "U19") (pin "L2") (pinfunction "PF9_L2_L2") (pintype "bidirectional"))
    )
    (net (code "275") (name "unconnected-(U19F-PF10_L1-PadL1)") (class "Default")
      (node (ref "U19") (pin "L1") (pinfunction "PF10_L1_L1") (pintype "bidirectional"))
    )
    (net (code "276") (name "unconnected-(U19F-PF11_R6-PadR6)") (class "Default")
      (node (ref "U19") (pin "R6") (pinfunction "PF11_R6_R6") (pintype "bidirectional"))
    )
    (net (code "277") (name "unconnected-(U19F-PF12_P6-PadP6)") (class "Default")
      (node (ref "U19") (pin "P6") (pinfunction "PF12_P6_P6") (pintype "bidirectional"))
    )
    (net (code "278") (name "unconnected-(U19F-PF13_N6-PadN6)") (class "Default")
      (node (ref "U19") (pin "N6") (pinfunction "PF13_N6_N6") (pintype "bidirectional"))
    )
    (net (code "279") (name "unconnected-(U19F-PF15_P7-PadP7)") (class "Default")
      (node (ref "U19") (pin "P7") (pinfunction "PF15_P7_P7") (pintype "bidirectional"))
    )
    (net (code "280") (name "unconnected-(U19G-PG0_N7-PadN7)") (class "Default")
      (node (ref "U19") (pin "N7") (pinfunction "PG0_N7_N7") (pintype "bidirectional"))
    )
    (net (code "281") (name "unconnected-(U19G-PG1_M7-PadM7)") (class "Default")
      (node (ref "U19") (pin "M7") (pinfunction "PG1_M7_M7") (pintype "bidirectional"))
    )
    (net (code "282") (name "unconnected-(U19G-PG2_L15-PadL15)") (class "Default")
      (node (ref "U19") (pin "L15") (pinfunction "PG2_L15_L15") (pintype "bidirectional"))
    )
    (net (code "283") (name "unconnected-(U19G-PG3_K15-PadK15)") (class "Default")
      (node (ref "U19") (pin "K15") (pinfunction "PG3_K15_K15") (pintype "bidirectional"))
    )
    (net (code "284") (name "unconnected-(U19G-PG4_K14-PadK14)") (class "Default")
      (node (ref "U19") (pin "K14") (pinfunction "PG4_K14_K14") (pintype "bidirectional"))
    )
    (net (code "285") (name "unconnected-(U19G-PG5_K13-PadK13)") (class "Default")
      (node (ref "U19") (pin "K13") (pinfunction "PG5_K13_K13") (pintype "bidirectional"))
    )
    (net (code "286") (name "unconnected-(U19G-PG8_H14-PadH14)") (class "Default")
      (node (ref "U19") (pin "H14") (pinfunction "PG8_H14_H14") (pintype "bidirectional"))
    )
    (net (code "287") (name "unconnected-(U19G-PG10_B10-PadB10)") (class "Default")
      (node (ref "U19") (pin "B10") (pinfunction "PG10_B10_B10") (pintype "bidirectional"))
    )
    (net (code "288") (name "unconnected-(U19G-PG11_B9-PadB9)") (class "Default")
      (node (ref "U19") (pin "B9") (pinfunction "PG11_B9_B9") (pintype "bidirectional"))
    )
    (net (code "289") (name "unconnected-(U19G-PG12_B8-PadB8)") (class "Default")
      (node (ref "U19") (pin "B8") (pinfunction "PG12_B8_B8") (pintype "bidirectional"))
    )
    (net (code "290") (name "unconnected-(U19G-PG13_A8-PadA8)") (class "Default")
      (node (ref "U19") (pin "A8") (pinfunction "PG13_A8_A8") (pintype "bidirectional"))
    )
    (net (code "291") (name "unconnected-(U19G-PG15_B7-PadB7)") (class "Default")
      (node (ref "U19") (pin "B7") (pinfunction "PG15_B7_B7") (pintype "bidirectional"))
    )
    (net (code "292") (name "unconnected-(U19H-PH1_H1-PadH1)") (class "Default")
      (node (ref "U19") (pin "H1") (pinfunction "PH1_H1_H1") (pintype "bidirectional"))
    )
    (net (code "293") (name "unconnected-(U19H-PH4_H4-PadH4)") (class "Default")
      (node (ref "U19") (pin "H4") (pinfunction "PH4_H4_H4") (pintype "bidirectional"))
    )
    (net (code "294") (name "unconnected-(U19H-PH5_J4-PadJ4)") (class "Default")
      (node (ref "U19") (pin "J4") (pinfunction "PH5_J4_J4") (pintype "bidirectional"))
    )
    (net (code "295") (name "unconnected-(U19H-PH6_M11-PadM11)") (class "Default")
      (node (ref "U19") (pin "M11") (pinfunction "PH6_M11_M11") (pintype "bidirectional"))
    )
    (net (code "296") (name "unconnected-(U19H-PH7_N12-PadN12)") (class "Default")
      (node (ref "U19") (pin "N12") (pinfunction "PH7_N12_N12") (pintype "bidirectional"))
    )
    (net (code "297") (name "unconnected-(U19H-PH8_M12-PadM12)") (class "Default")
      (node (ref "U19") (pin "M12") (pinfunction "PH8_M12_M12") (pintype "bidirectional"))
    )
    (net (code "298") (name "unconnected-(U19H-PH9_M13-PadM13)") (class "Default")
      (node (ref "U19") (pin "M13") (pinfunction "PH9_M13_M13") (pintype "bidirectional"))
    )
    (net (code "299") (name "unconnected-(U19H-PH10_L13-PadL13)") (class "Default")
      (node (ref "U19") (pin "L13") (pinfunction "PH10_L13_L13") (pintype "bidirectional"))
    )
    (net (code "300") (name "unconnected-(U19H-PH11_L12-PadL12)") (class "Default")
      (node (ref "U19") (pin "L12") (pinfunction "PH11_L12_L12") (pintype "bidirectional"))
    )
    (net (code "301") (name "unconnected-(U19H-PH12_K12-PadK12)") (class "Default")
      (node (ref "U19") (pin "K12") (pinfunction "PH12_K12_K12") (pintype "bidirectional"))
    )
    (net (code "302") (name "unconnected-(U19H-PH13_E12-PadE12)") (class "Default")
      (node (ref "U19") (pin "E12") (pinfunction "PH13_E12_E12") (pintype "bidirectional"))
    )
    (net (code "303") (name "unconnected-(U19H-PH14_E13-PadE13)") (class "Default")
      (node (ref "U19") (pin "E13") (pinfunction "PH14_E13_E13") (pintype "bidirectional"))
    )
    (net (code "304") (name "unconnected-(U19H-PH15_D13-PadD13)") (class "Default")
      (node (ref "U19") (pin "D13") (pinfunction "PH15_D13_D13") (pintype "bidirectional"))
    )
    (net (code "305") (name "unconnected-(U19I-PI0_E14-PadE14)") (class "Default")
      (node (ref "U19") (pin "E14") (pinfunction "PI0_E14_E14") (pintype "bidirectional"))
    )
    (net (code "306") (name "unconnected-(U19I-PI1_D14-PadD14)") (class "Default")
      (node (ref "U19") (pin "D14") (pinfunction "PI1_D14_D14") (pintype "bidirectional"))
    )
    (net (code "307") (name "unconnected-(U19I-PI2_C14-PadC14)") (class "Default")
      (node (ref "U19") (pin "C14") (pinfunction "PI2_C14_C14") (pintype "bidirectional"))
    )
    (net (code "308") (name "unconnected-(U19I-PI3_C13-PadC13)") (class "Default")
      (node (ref "U19") (pin "C13") (pinfunction "PI3_C13_C13") (pintype "bidirectional"))
    )
    (net (code "309") (name "unconnected-(U19I-PI4_D4-PadD4)") (class "Default")
      (node (ref "U19") (pin "D4") (pinfunction "PI4_D4_D4") (pintype "bidirectional"))
    )
    (net (code "310") (name "unconnected-(U19I-PI5_C4-PadC4)") (class "Default")
      (node (ref "U19") (pin "C4") (pinfunction "PI5_C4_C4") (pintype "bidirectional"))
    )
    (net (code "311") (name "unconnected-(U19I-PI8_D2-PadD2)") (class "Default")
      (node (ref "U19") (pin "D2") (pinfunction "PI8_D2_D2") (pintype "bidirectional"))
    )
    (net (code "312") (name "unconnected-(U19I-PI9_D3-PadD3)") (class "Default")
      (node (ref "U19") (pin "D3") (pinfunction "PI9_D3_D3") (pintype "bidirectional"))
    )
    (net (code "313") (name "unconnected-(U19I-PI10_E3-PadE3)") (class "Default")
      (node (ref "U19") (pin "E3") (pinfunction "PI10_E3_E3") (pintype "bidirectional"))
    )
    (net (code "314") (name "unconnected-(U19I-PI11_E4-PadE4)") (class "Default")
      (node (ref "U19") (pin "E4") (pinfunction "PI11_E4_E4") (pintype "bidirectional"))
    )
  )
)
